# testeri_V1_1.net
KiCad netlist of a schematic drawn in EAGLE
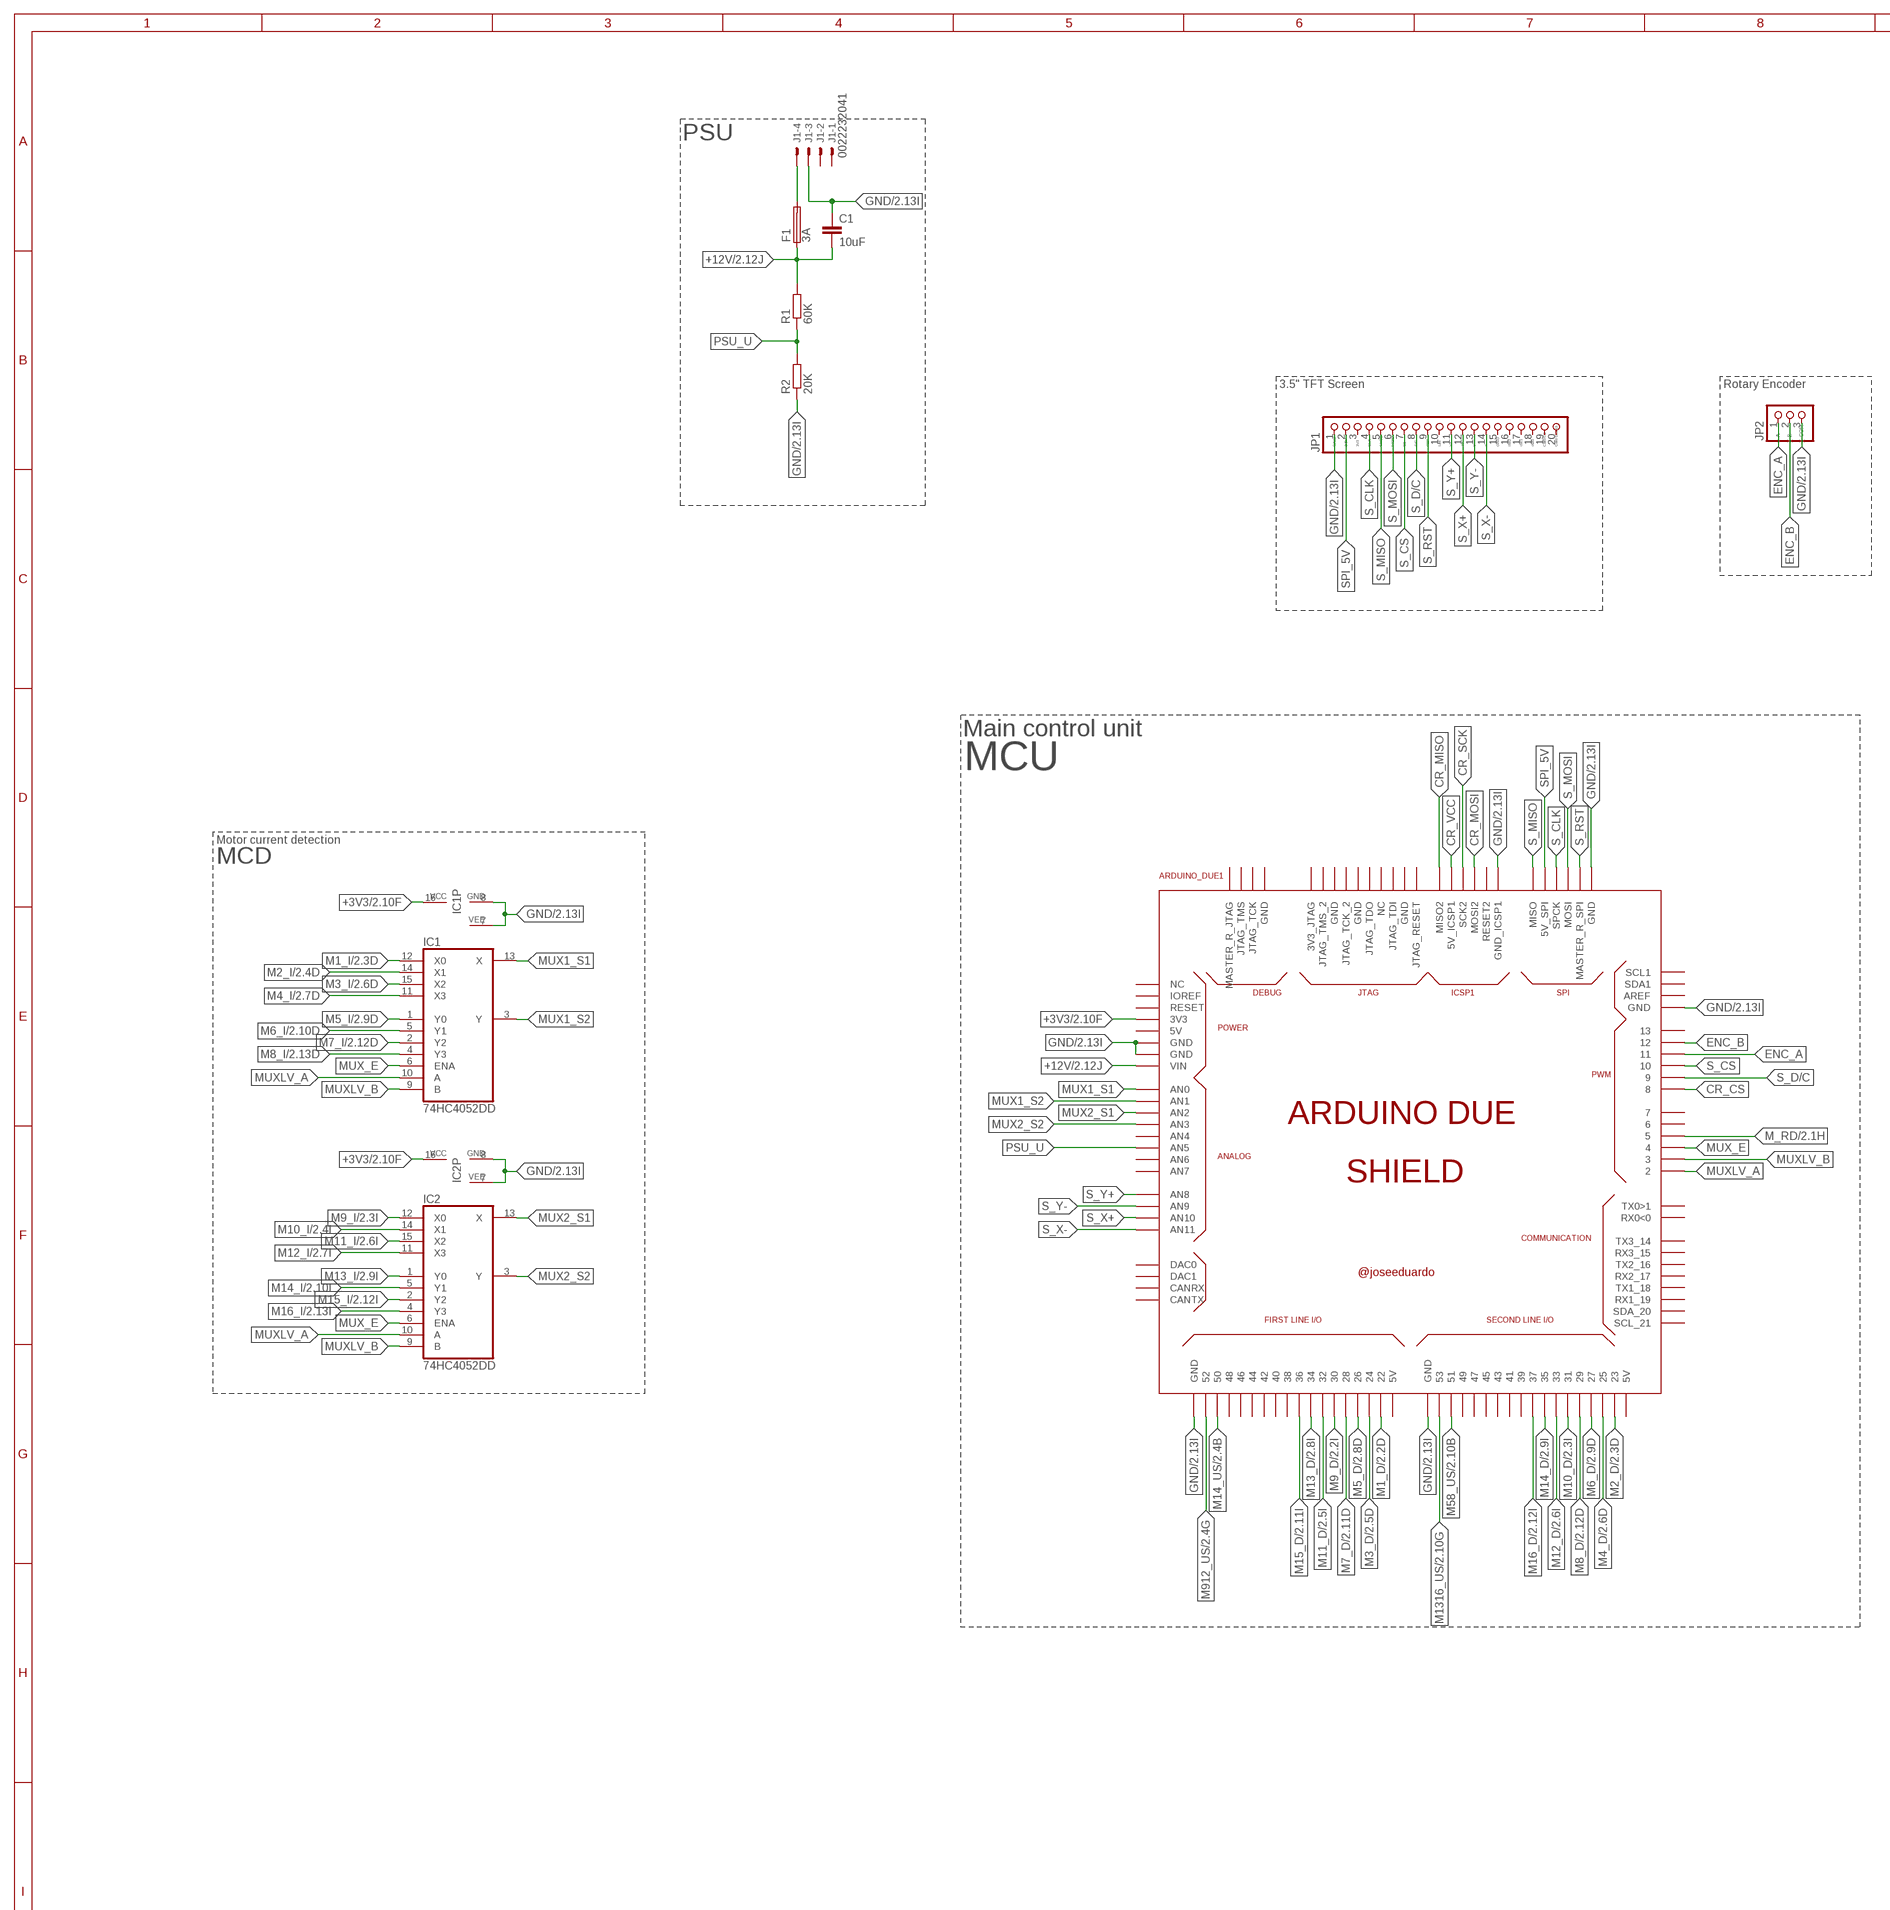
[diagram p0: schematic, sheet 1, part 1 of 2]
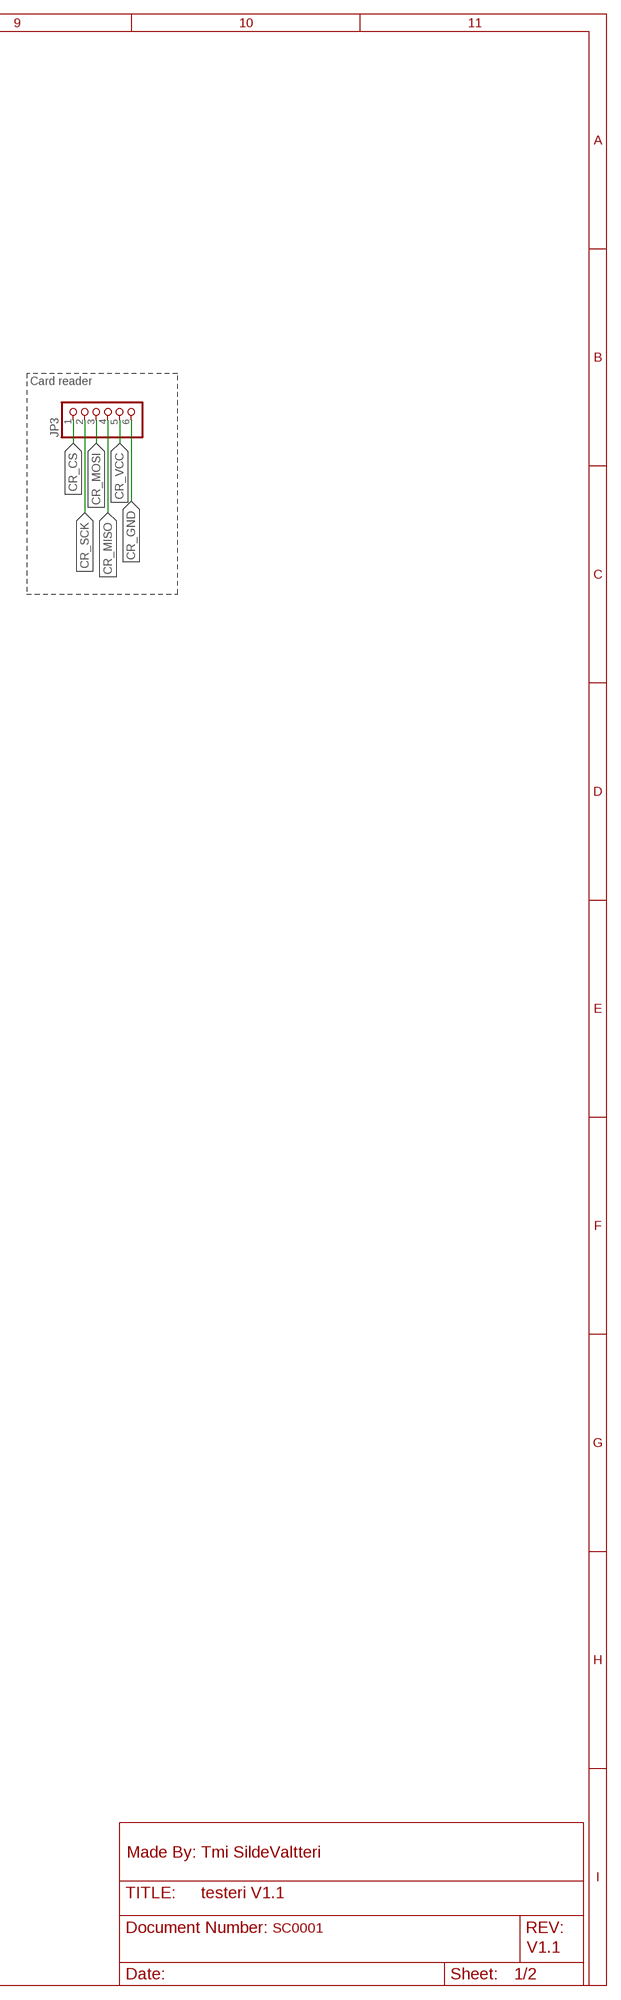
[diagram p1: schematic, sheet 1, part 2 of 2]
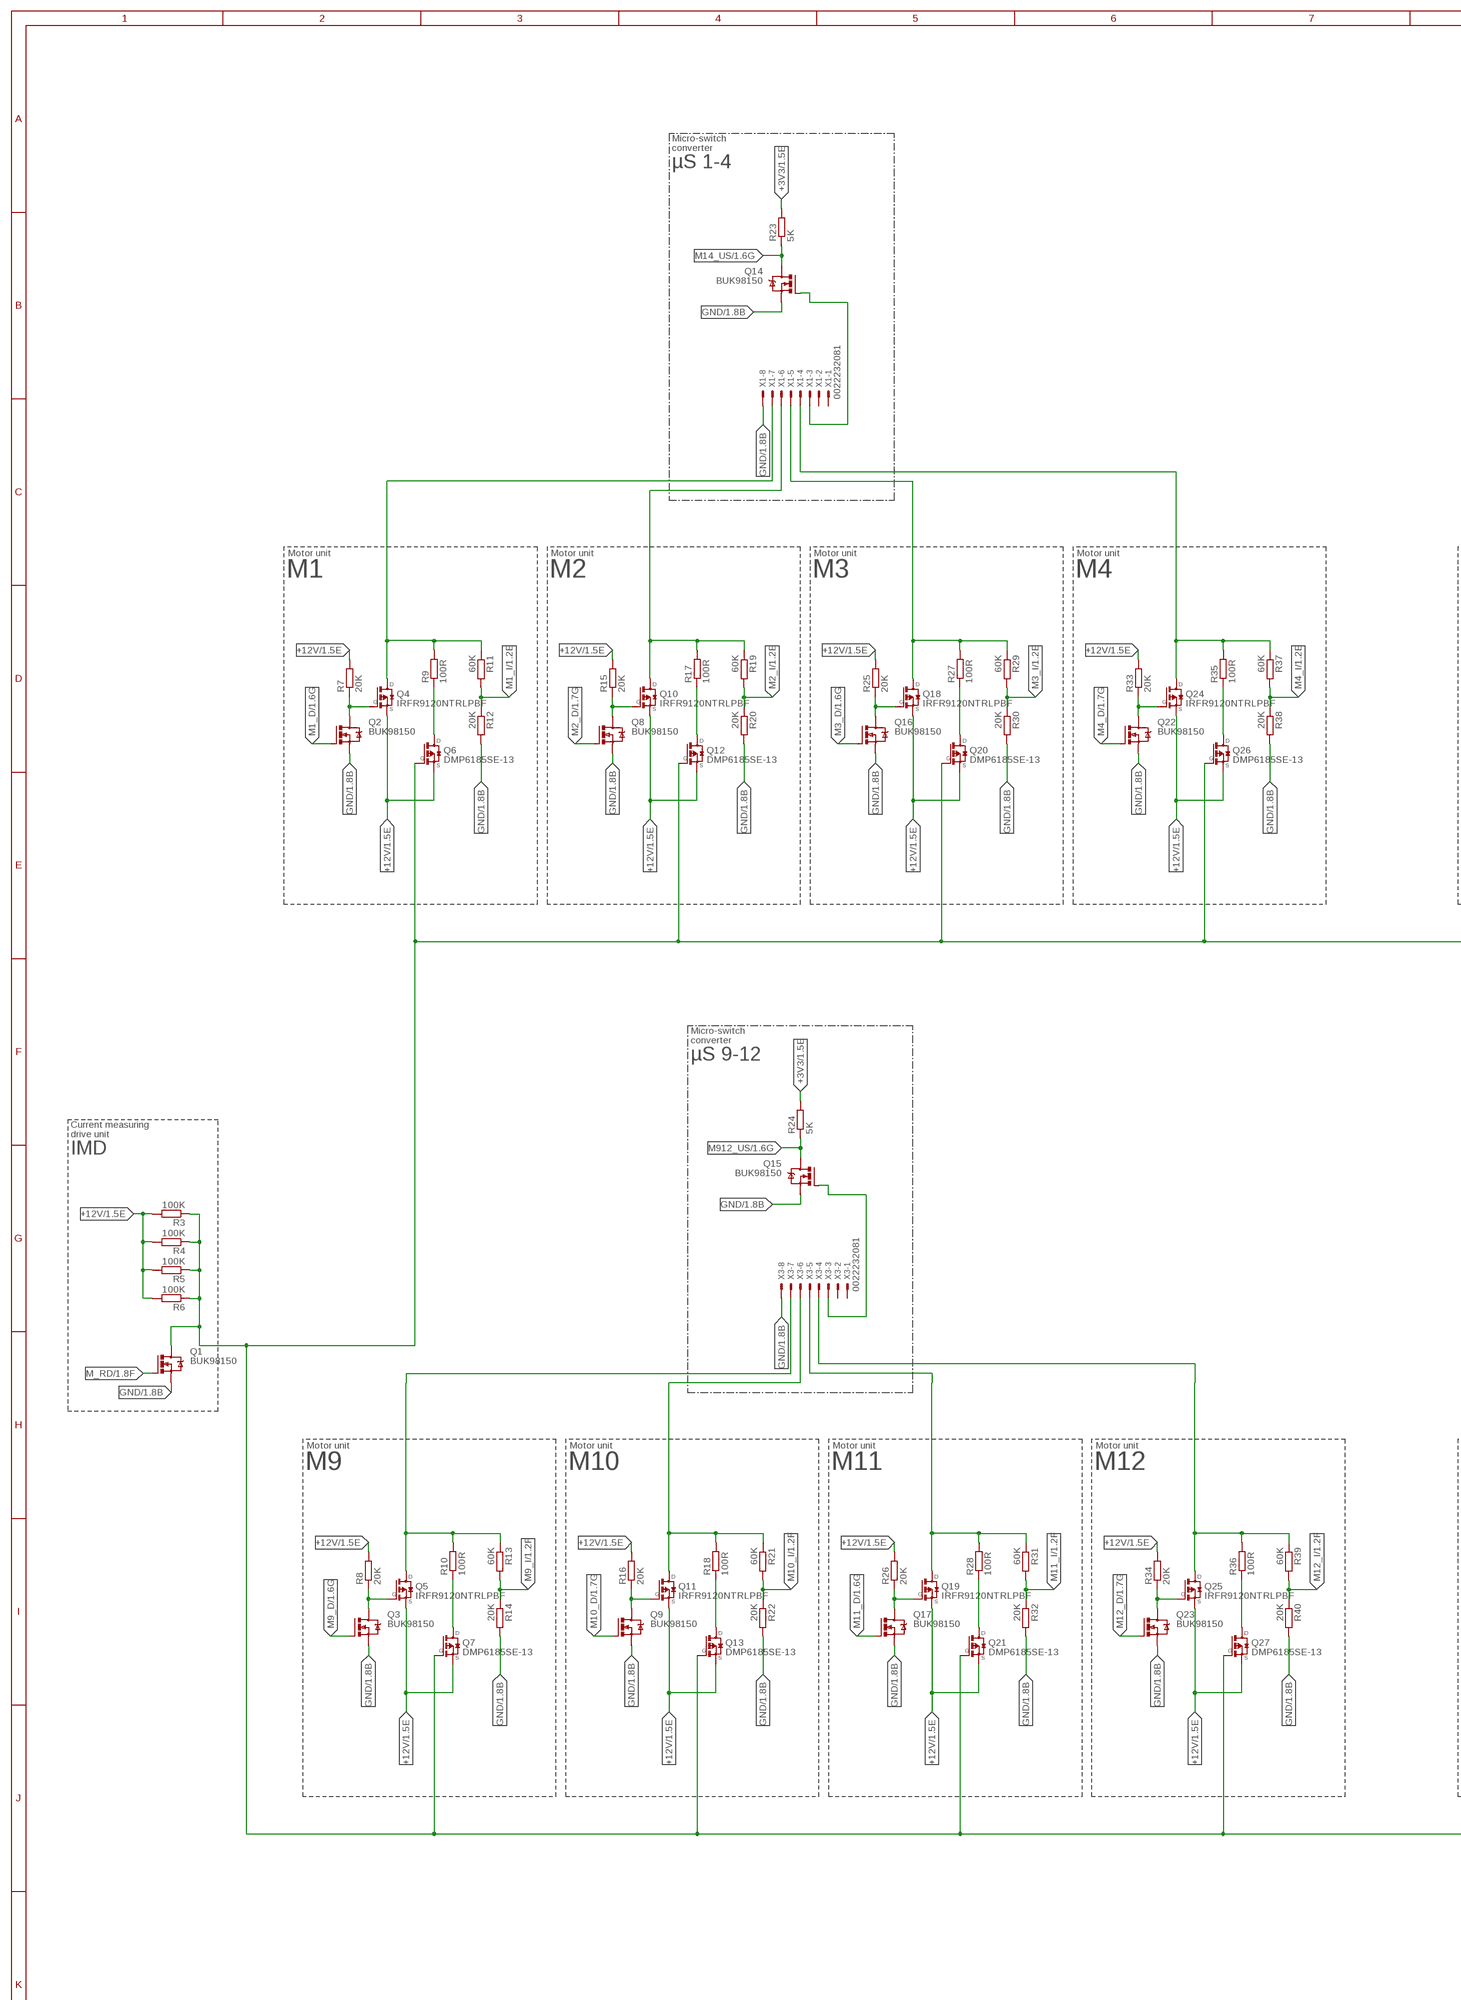
[diagram p2: schematic, sheet 2, part 1 of 3]
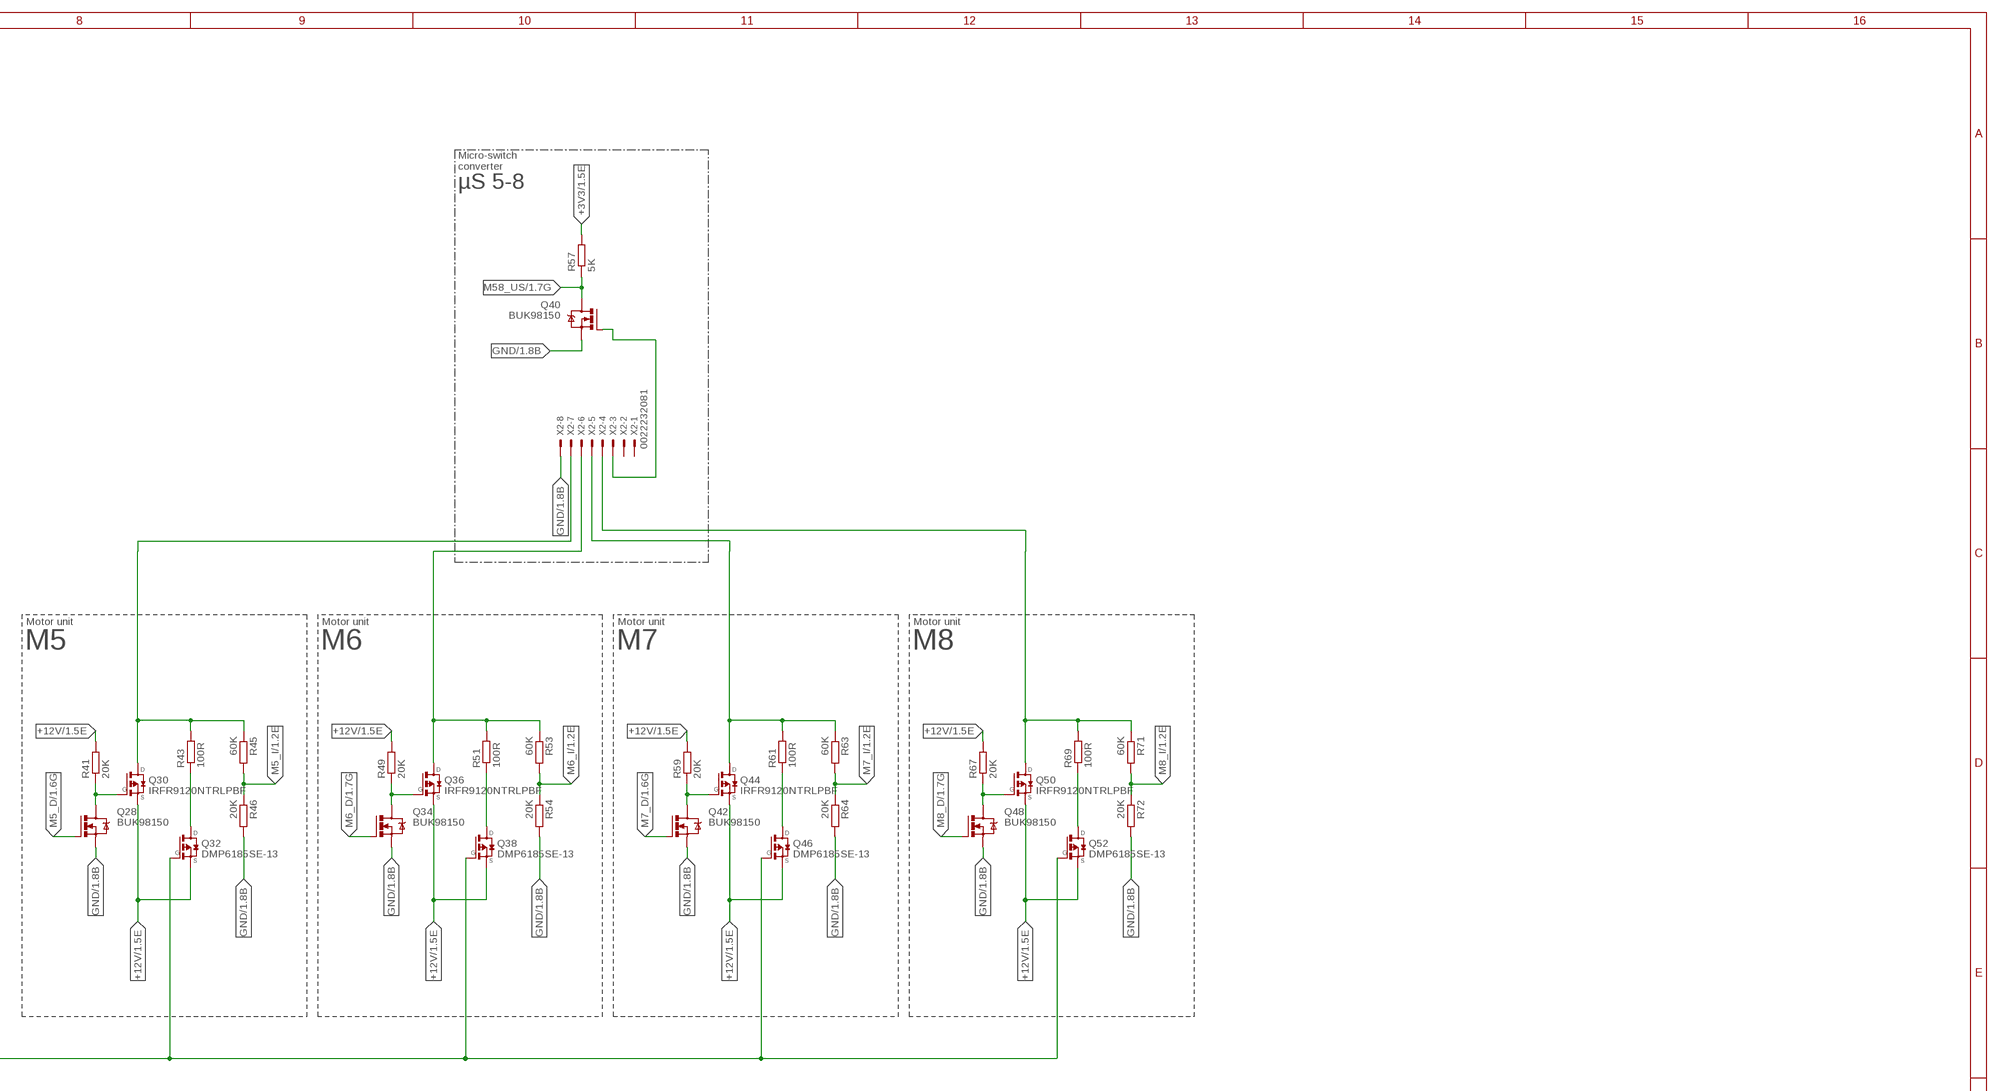
[diagram p3: schematic, sheet 2, part 2 of 3]
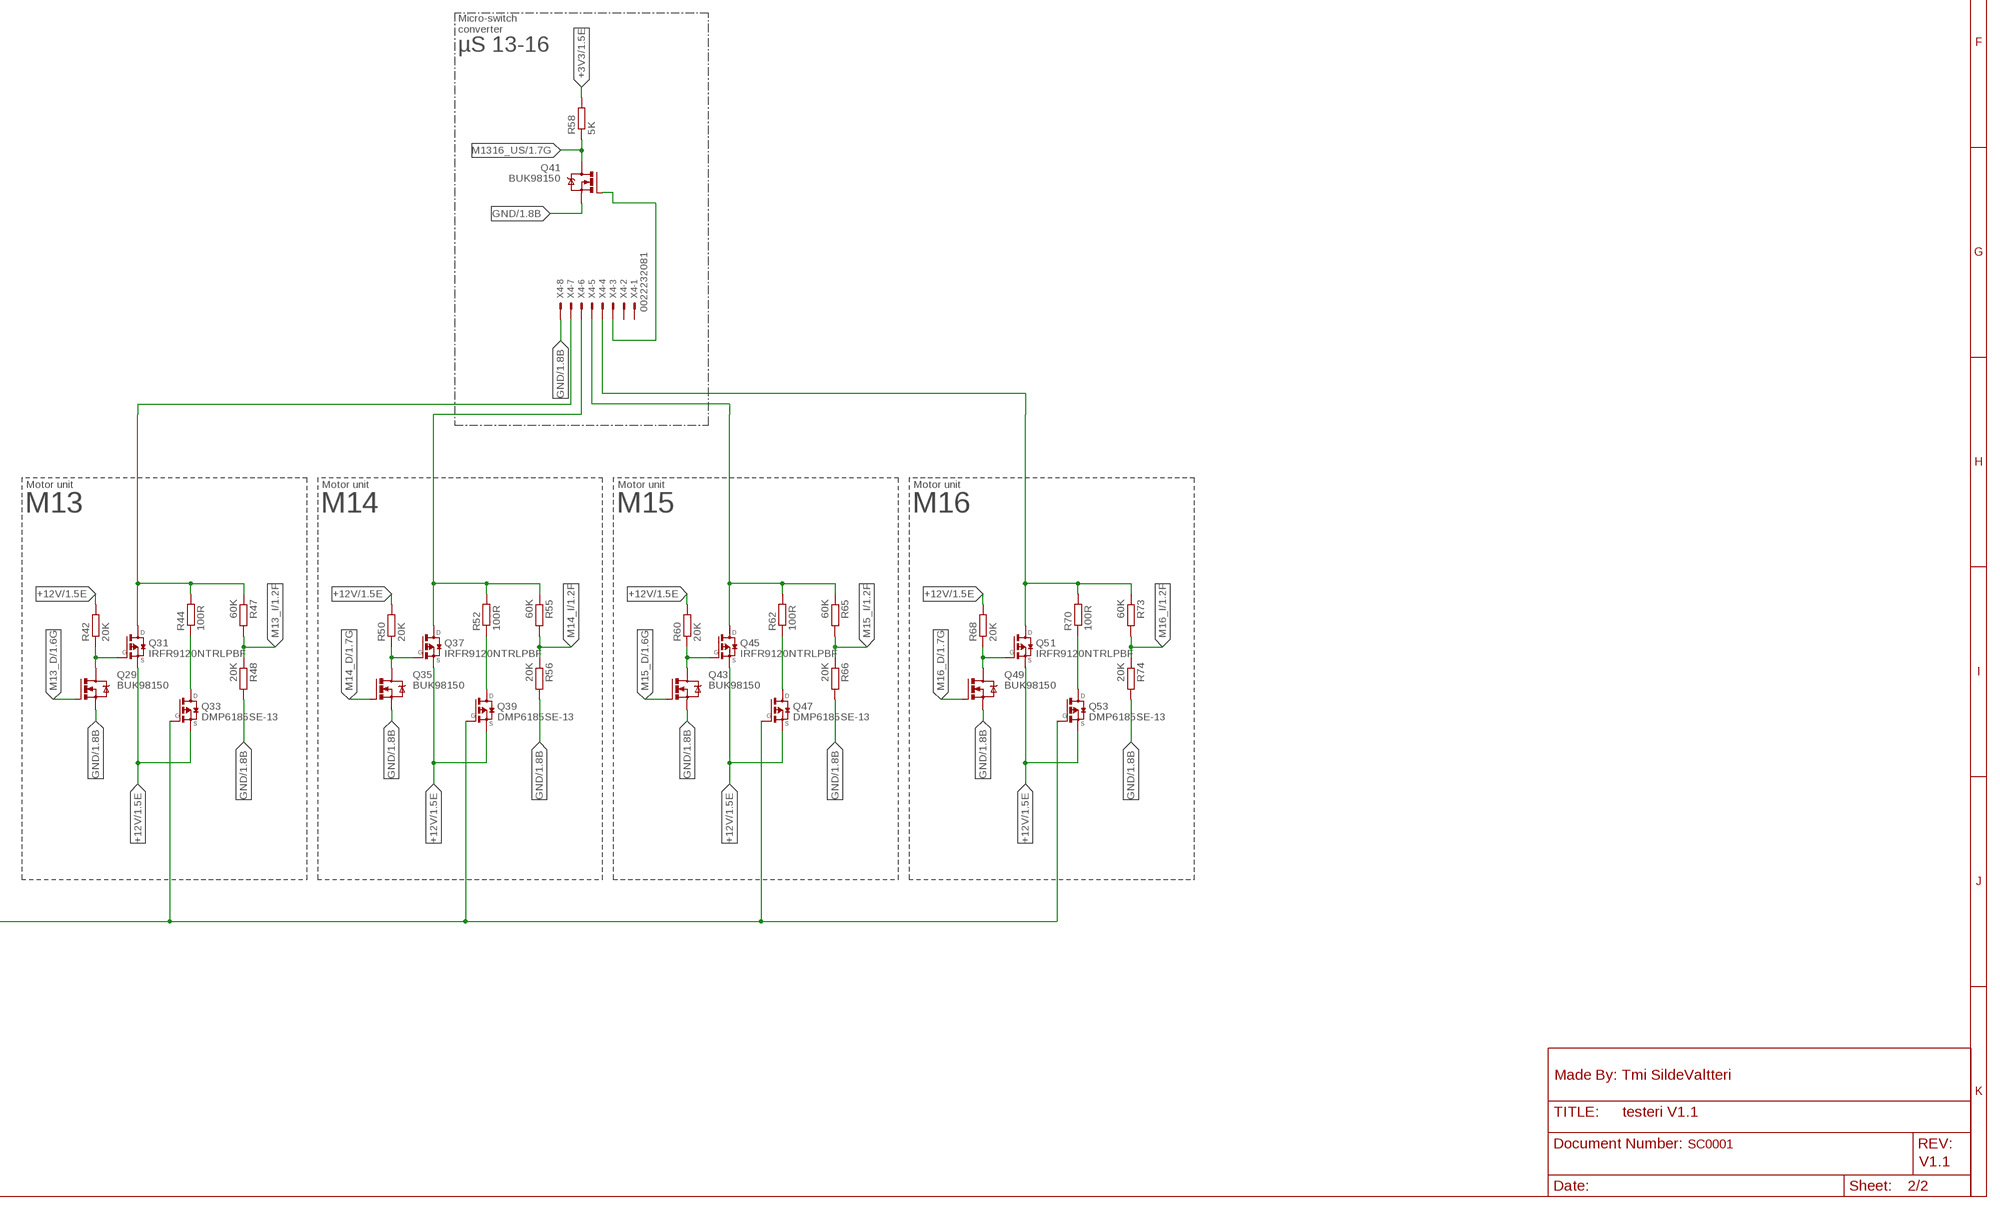
[diagram p4: schematic, sheet 2, part 3 of 3]

(export (version "E")
  (design (tool "Eeschema 10.0.6"))
  (components
    (comp (ref "Q1")
      (value "BUK98150")
      (footprint "eagle-import:SOT223")
      (libsource (lib "eagle-import") (part "BUK98150"))
    )
    (comp (ref "Q2")
      (value "BUK98150")
      (footprint "eagle-import:SOT223")
      (libsource (lib "eagle-import") (part "BUK98150"))
    )
    (comp (ref "Q3")
      (value "BUK98150")
      (footprint "eagle-import:SOT223")
      (libsource (lib "eagle-import") (part "BUK98150"))
    )
    (comp (ref "Q4")
      (value "IRFR9120NTRLPBF")
      (footprint "eagle-import:D-PAK_TO252AA")
      (libsource (lib "eagle-import") (part "IRFR9120NTRLPBF"))
    )
    (comp (ref "Q5")
      (value "IRFR9120NTRLPBF")
      (footprint "eagle-import:D-PAK_TO252AA")
      (libsource (lib "eagle-import") (part "IRFR9120NTRLPBF"))
    )
    (comp (ref "Q6")
      (value "DMP6185SE-13")
      (footprint "eagle-import:SOT223")
      (libsource (lib "eagle-import") (part "DMP6185SE-13"))
    )
    (comp (ref "Q7")
      (value "DMP6185SE-13")
      (footprint "eagle-import:SOT223")
      (libsource (lib "eagle-import") (part "DMP6185SE-13"))
    )
    (comp (ref "Q8")
      (value "BUK98150")
      (footprint "eagle-import:SOT223")
      (libsource (lib "eagle-import") (part "BUK98150"))
    )
    (comp (ref "Q9")
      (value "BUK98150")
      (footprint "eagle-import:SOT223")
      (libsource (lib "eagle-import") (part "BUK98150"))
    )
    (comp (ref "Q10")
      (value "IRFR9120NTRLPBF")
      (footprint "eagle-import:D-PAK_TO252AA")
      (libsource (lib "eagle-import") (part "IRFR9120NTRLPBF"))
    )
    (comp (ref "Q11")
      (value "IRFR9120NTRLPBF")
      (footprint "eagle-import:D-PAK_TO252AA")
      (libsource (lib "eagle-import") (part "IRFR9120NTRLPBF"))
    )
    (comp (ref "Q12")
      (value "DMP6185SE-13")
      (footprint "eagle-import:SOT223")
      (libsource (lib "eagle-import") (part "DMP6185SE-13"))
    )
    (comp (ref "Q13")
      (value "DMP6185SE-13")
      (footprint "eagle-import:SOT223")
      (libsource (lib "eagle-import") (part "DMP6185SE-13"))
    )
    (comp (ref "Q14")
      (value "BUK98150")
      (footprint "eagle-import:SOT223")
      (libsource (lib "eagle-import") (part "BUK98150"))
    )
    (comp (ref "Q15")
      (value "BUK98150")
      (footprint "eagle-import:SOT223")
      (libsource (lib "eagle-import") (part "BUK98150"))
    )
    (comp (ref "Q16")
      (value "BUK98150")
      (footprint "eagle-import:SOT223")
      (libsource (lib "eagle-import") (part "BUK98150"))
    )
    (comp (ref "Q17")
      (value "BUK98150")
      (footprint "eagle-import:SOT223")
      (libsource (lib "eagle-import") (part "BUK98150"))
    )
    (comp (ref "Q18")
      (value "IRFR9120NTRLPBF")
      (footprint "eagle-import:D-PAK_TO252AA")
      (libsource (lib "eagle-import") (part "IRFR9120NTRLPBF"))
    )
    (comp (ref "Q19")
      (value "IRFR9120NTRLPBF")
      (footprint "eagle-import:D-PAK_TO252AA")
      (libsource (lib "eagle-import") (part "IRFR9120NTRLPBF"))
    )
    (comp (ref "Q20")
      (value "DMP6185SE-13")
      (footprint "eagle-import:SOT223")
      (libsource (lib "eagle-import") (part "DMP6185SE-13"))
    )
    (comp (ref "Q21")
      (value "DMP6185SE-13")
      (footprint "eagle-import:SOT223")
      (libsource (lib "eagle-import") (part "DMP6185SE-13"))
    )
    (comp (ref "Q22")
      (value "BUK98150")
      (footprint "eagle-import:SOT223")
      (libsource (lib "eagle-import") (part "BUK98150"))
    )
    (comp (ref "Q23")
      (value "BUK98150")
      (footprint "eagle-import:SOT223")
      (libsource (lib "eagle-import") (part "BUK98150"))
    )
    (comp (ref "Q24")
      (value "IRFR9120NTRLPBF")
      (footprint "eagle-import:D-PAK_TO252AA")
      (libsource (lib "eagle-import") (part "IRFR9120NTRLPBF"))
    )
    (comp (ref "Q25")
      (value "IRFR9120NTRLPBF")
      (footprint "eagle-import:D-PAK_TO252AA")
      (libsource (lib "eagle-import") (part "IRFR9120NTRLPBF"))
    )
    (comp (ref "Q26")
      (value "DMP6185SE-13")
      (footprint "eagle-import:SOT223")
      (libsource (lib "eagle-import") (part "DMP6185SE-13"))
    )
    (comp (ref "Q27")
      (value "DMP6185SE-13")
      (footprint "eagle-import:SOT223")
      (libsource (lib "eagle-import") (part "DMP6185SE-13"))
    )
    (comp (ref "Q28")
      (value "BUK98150")
      (footprint "eagle-import:SOT223")
      (libsource (lib "eagle-import") (part "BUK98150"))
    )
    (comp (ref "Q29")
      (value "BUK98150")
      (footprint "eagle-import:SOT223")
      (libsource (lib "eagle-import") (part "BUK98150"))
    )
    (comp (ref "Q30")
      (value "IRFR9120NTRLPBF")
      (footprint "eagle-import:D-PAK_TO252AA")
      (libsource (lib "eagle-import") (part "IRFR9120NTRLPBF"))
    )
    (comp (ref "Q31")
      (value "IRFR9120NTRLPBF")
      (footprint "eagle-import:D-PAK_TO252AA")
      (libsource (lib "eagle-import") (part "IRFR9120NTRLPBF"))
    )
    (comp (ref "Q32")
      (value "DMP6185SE-13")
      (footprint "eagle-import:SOT223")
      (libsource (lib "eagle-import") (part "DMP6185SE-13"))
    )
    (comp (ref "Q33")
      (value "DMP6185SE-13")
      (footprint "eagle-import:SOT223")
      (libsource (lib "eagle-import") (part "DMP6185SE-13"))
    )
    (comp (ref "Q34")
      (value "BUK98150")
      (footprint "eagle-import:SOT223")
      (libsource (lib "eagle-import") (part "BUK98150"))
    )
    (comp (ref "Q35")
      (value "BUK98150")
      (footprint "eagle-import:SOT223")
      (libsource (lib "eagle-import") (part "BUK98150"))
    )
    (comp (ref "Q36")
      (value "IRFR9120NTRLPBF")
      (footprint "eagle-import:D-PAK_TO252AA")
      (libsource (lib "eagle-import") (part "IRFR9120NTRLPBF"))
    )
    (comp (ref "Q37")
      (value "IRFR9120NTRLPBF")
      (footprint "eagle-import:D-PAK_TO252AA")
      (libsource (lib "eagle-import") (part "IRFR9120NTRLPBF"))
    )
    (comp (ref "Q38")
      (value "DMP6185SE-13")
      (footprint "eagle-import:SOT223")
      (libsource (lib "eagle-import") (part "DMP6185SE-13"))
    )
    (comp (ref "Q39")
      (value "DMP6185SE-13")
      (footprint "eagle-import:SOT223")
      (libsource (lib "eagle-import") (part "DMP6185SE-13"))
    )
    (comp (ref "Q40")
      (value "BUK98150")
      (footprint "eagle-import:SOT223")
      (libsource (lib "eagle-import") (part "BUK98150"))
    )
    (comp (ref "Q41")
      (value "BUK98150")
      (footprint "eagle-import:SOT223")
      (libsource (lib "eagle-import") (part "BUK98150"))
    )
    (comp (ref "Q42")
      (value "BUK98150")
      (footprint "eagle-import:SOT223")
      (libsource (lib "eagle-import") (part "BUK98150"))
    )
    (comp (ref "Q43")
      (value "BUK98150")
      (footprint "eagle-import:SOT223")
      (libsource (lib "eagle-import") (part "BUK98150"))
    )
    (comp (ref "Q44")
      (value "IRFR9120NTRLPBF")
      (footprint "eagle-import:D-PAK_TO252AA")
      (libsource (lib "eagle-import") (part "IRFR9120NTRLPBF"))
    )
    (comp (ref "Q45")
      (value "IRFR9120NTRLPBF")
      (footprint "eagle-import:D-PAK_TO252AA")
      (libsource (lib "eagle-import") (part "IRFR9120NTRLPBF"))
    )
    (comp (ref "Q46")
      (value "DMP6185SE-13")
      (footprint "eagle-import:SOT223")
      (libsource (lib "eagle-import") (part "DMP6185SE-13"))
    )
    (comp (ref "Q47")
      (value "DMP6185SE-13")
      (footprint "eagle-import:SOT223")
      (libsource (lib "eagle-import") (part "DMP6185SE-13"))
    )
    (comp (ref "Q48")
      (value "BUK98150")
      (footprint "eagle-import:SOT223")
      (libsource (lib "eagle-import") (part "BUK98150"))
    )
    (comp (ref "Q49")
      (value "BUK98150")
      (footprint "eagle-import:SOT223")
      (libsource (lib "eagle-import") (part "BUK98150"))
    )
    (comp (ref "Q50")
      (value "IRFR9120NTRLPBF")
      (footprint "eagle-import:D-PAK_TO252AA")
      (libsource (lib "eagle-import") (part "IRFR9120NTRLPBF"))
    )
    (comp (ref "Q51")
      (value "IRFR9120NTRLPBF")
      (footprint "eagle-import:D-PAK_TO252AA")
      (libsource (lib "eagle-import") (part "IRFR9120NTRLPBF"))
    )
    (comp (ref "Q52")
      (value "DMP6185SE-13")
      (footprint "eagle-import:SOT223")
      (libsource (lib "eagle-import") (part "DMP6185SE-13"))
    )
    (comp (ref "Q53")
      (value "DMP6185SE-13")
      (footprint "eagle-import:SOT223")
      (libsource (lib "eagle-import") (part "DMP6185SE-13"))
    )
    (comp (ref "R3")
      (value "100K")
      (footprint "eagle-import:R3216W")
      (libsource (lib "eagle-import") (part "R-EU_R3216W"))
    )
    (comp (ref "R4")
      (value "100K")
      (footprint "eagle-import:R3216W")
      (libsource (lib "eagle-import") (part "R-EU_R3216W"))
    )
    (comp (ref "R5")
      (value "100K")
      (footprint "eagle-import:R3216W")
      (libsource (lib "eagle-import") (part "R-EU_R3216W"))
    )
    (comp (ref "R6")
      (value "100K")
      (footprint "eagle-import:R3216W")
      (libsource (lib "eagle-import") (part "R-EU_R3216W"))
    )
    (comp (ref "R7")
      (value "20K")
      (footprint "eagle-import:R3216W")
      (libsource (lib "eagle-import") (part "R-EU_R3216W"))
    )
    (comp (ref "R8")
      (value "20K")
      (footprint "eagle-import:R3216W")
      (libsource (lib "eagle-import") (part "R-EU_R3216W"))
    )
    (comp (ref "R9")
      (value "100R")
      (footprint "eagle-import:0411_15")
      (libsource (lib "eagle-import") (part "R-EU_0411/15"))
    )
    (comp (ref "R10")
      (value "100R")
      (footprint "eagle-import:0411_15")
      (libsource (lib "eagle-import") (part "R-EU_0411/15"))
    )
    (comp (ref "R11")
      (value "60K")
      (footprint "eagle-import:R3216W")
      (libsource (lib "eagle-import") (part "R-EU_R3216W"))
    )
    (comp (ref "R12")
      (value "20K")
      (footprint "eagle-import:R3216W")
      (libsource (lib "eagle-import") (part "R-EU_R3216W"))
    )
    (comp (ref "R13")
      (value "60K")
      (footprint "eagle-import:R3216W")
      (libsource (lib "eagle-import") (part "R-EU_R3216W"))
    )
    (comp (ref "R14")
      (value "20K")
      (footprint "eagle-import:R3216W")
      (libsource (lib "eagle-import") (part "R-EU_R3216W"))
    )
    (comp (ref "R15")
      (value "20K")
      (footprint "eagle-import:R3216W")
      (libsource (lib "eagle-import") (part "R-EU_R3216W"))
    )
    (comp (ref "R16")
      (value "20K")
      (footprint "eagle-import:R3216W")
      (libsource (lib "eagle-import") (part "R-EU_R3216W"))
    )
    (comp (ref "R17")
      (value "100R")
      (footprint "eagle-import:0411_15")
      (libsource (lib "eagle-import") (part "R-EU_0411/15"))
    )
    (comp (ref "R18")
      (value "100R")
      (footprint "eagle-import:0411_15")
      (libsource (lib "eagle-import") (part "R-EU_0411/15"))
    )
    (comp (ref "R19")
      (value "60K")
      (footprint "eagle-import:R3216W")
      (libsource (lib "eagle-import") (part "R-EU_R3216W"))
    )
    (comp (ref "R20")
      (value "20K")
      (footprint "eagle-import:R3216W")
      (libsource (lib "eagle-import") (part "R-EU_R3216W"))
    )
    (comp (ref "R21")
      (value "60K")
      (footprint "eagle-import:R3216W")
      (libsource (lib "eagle-import") (part "R-EU_R3216W"))
    )
    (comp (ref "R22")
      (value "20K")
      (footprint "eagle-import:R3216W")
      (libsource (lib "eagle-import") (part "R-EU_R3216W"))
    )
    (comp (ref "R23")
      (value "5K")
      (footprint "eagle-import:R3216W")
      (libsource (lib "eagle-import") (part "R-EU_R3216W"))
    )
    (comp (ref "R24")
      (value "5K")
      (footprint "eagle-import:R3216W")
      (libsource (lib "eagle-import") (part "R-EU_R3216W"))
    )
    (comp (ref "R25")
      (value "20K")
      (footprint "eagle-import:R3216W")
      (libsource (lib "eagle-import") (part "R-EU_R3216W"))
    )
    (comp (ref "R26")
      (value "20K")
      (footprint "eagle-import:R3216W")
      (libsource (lib "eagle-import") (part "R-EU_R3216W"))
    )
    (comp (ref "R27")
      (value "100R")
      (footprint "eagle-import:0411_15")
      (libsource (lib "eagle-import") (part "R-EU_0411/15"))
    )
    (comp (ref "R28")
      (value "100R")
      (footprint "eagle-import:0411_15")
      (libsource (lib "eagle-import") (part "R-EU_0411/15"))
    )
    (comp (ref "R29")
      (value "60K")
      (footprint "eagle-import:R3216W")
      (libsource (lib "eagle-import") (part "R-EU_R3216W"))
    )
    (comp (ref "R30")
      (value "20K")
      (footprint "eagle-import:R3216W")
      (libsource (lib "eagle-import") (part "R-EU_R3216W"))
    )
    (comp (ref "R31")
      (value "60K")
      (footprint "eagle-import:R3216W")
      (libsource (lib "eagle-import") (part "R-EU_R3216W"))
    )
    (comp (ref "R32")
      (value "20K")
      (footprint "eagle-import:R3216W")
      (libsource (lib "eagle-import") (part "R-EU_R3216W"))
    )
    (comp (ref "R33")
      (value "20K")
      (footprint "eagle-import:R3216W")
      (libsource (lib "eagle-import") (part "R-EU_R3216W"))
    )
    (comp (ref "R34")
      (value "20K")
      (footprint "eagle-import:R3216W")
      (libsource (lib "eagle-import") (part "R-EU_R3216W"))
    )
    (comp (ref "R35")
      (value "100R")
      (footprint "eagle-import:0411_15")
      (libsource (lib "eagle-import") (part "R-EU_0411/15"))
    )
    (comp (ref "R36")
      (value "100R")
      (footprint "eagle-import:0411_15")
      (libsource (lib "eagle-import") (part "R-EU_0411/15"))
    )
    (comp (ref "R37")
      (value "60K")
      (footprint "eagle-import:R3216W")
      (libsource (lib "eagle-import") (part "R-EU_R3216W"))
    )
    (comp (ref "R38")
      (value "20K")
      (footprint "eagle-import:R3216W")
      (libsource (lib "eagle-import") (part "R-EU_R3216W"))
    )
    (comp (ref "R39")
      (value "60K")
      (footprint "eagle-import:R3216W")
      (libsource (lib "eagle-import") (part "R-EU_R3216W"))
    )
    (comp (ref "R40")
      (value "20K")
      (footprint "eagle-import:R3216W")
      (libsource (lib "eagle-import") (part "R-EU_R3216W"))
    )
    (comp (ref "R41")
      (value "20K")
      (footprint "eagle-import:R3216W")
      (libsource (lib "eagle-import") (part "R-EU_R3216W"))
    )
    (comp (ref "R42")
      (value "20K")
      (footprint "eagle-import:R3216W")
      (libsource (lib "eagle-import") (part "R-EU_R3216W"))
    )
    (comp (ref "R43")
      (value "100R")
      (footprint "eagle-import:0411_15")
      (libsource (lib "eagle-import") (part "R-EU_0411/15"))
    )
    (comp (ref "R44")
      (value "100R")
      (footprint "eagle-import:0411_15")
      (libsource (lib "eagle-import") (part "R-EU_0411/15"))
    )
    (comp (ref "R45")
      (value "60K")
      (footprint "eagle-import:R3216W")
      (libsource (lib "eagle-import") (part "R-EU_R3216W"))
    )
    (comp (ref "R46")
      (value "20K")
      (footprint "eagle-import:R3216W")
      (libsource (lib "eagle-import") (part "R-EU_R3216W"))
    )
    (comp (ref "R47")
      (value "60K")
      (footprint "eagle-import:R3216W")
      (libsource (lib "eagle-import") (part "R-EU_R3216W"))
    )
    (comp (ref "R48")
      (value "20K")
      (footprint "eagle-import:R3216W")
      (libsource (lib "eagle-import") (part "R-EU_R3216W"))
    )
    (comp (ref "R49")
      (value "20K")
      (footprint "eagle-import:R3216W")
      (libsource (lib "eagle-import") (part "R-EU_R3216W"))
    )
    (comp (ref "R50")
      (value "20K")
      (footprint "eagle-import:R3216W")
      (libsource (lib "eagle-import") (part "R-EU_R3216W"))
    )
    (comp (ref "R51")
      (value "100R")
      (footprint "eagle-import:0411_15")
      (libsource (lib "eagle-import") (part "R-EU_0411/15"))
    )
    (comp (ref "R52")
      (value "100R")
      (footprint "eagle-import:0411_15")
      (libsource (lib "eagle-import") (part "R-EU_0411/15"))
    )
    (comp (ref "R53")
      (value "60K")
      (footprint "eagle-import:R3216W")
      (libsource (lib "eagle-import") (part "R-EU_R3216W"))
    )
    (comp (ref "R54")
      (value "20K")
      (footprint "eagle-import:R3216W")
      (libsource (lib "eagle-import") (part "R-EU_R3216W"))
    )
    (comp (ref "R55")
      (value "60K")
      (footprint "eagle-import:R3216W")
      (libsource (lib "eagle-import") (part "R-EU_R3216W"))
    )
    (comp (ref "R56")
      (value "20K")
      (footprint "eagle-import:R3216W")
      (libsource (lib "eagle-import") (part "R-EU_R3216W"))
    )
    (comp (ref "R57")
      (value "5K")
      (footprint "eagle-import:R3216W")
      (libsource (lib "eagle-import") (part "R-EU_R3216W"))
    )
    (comp (ref "R58")
      (value "5K")
      (footprint "eagle-import:R3216W")
      (libsource (lib "eagle-import") (part "R-EU_R3216W"))
    )
    (comp (ref "R59")
      (value "20K")
      (footprint "eagle-import:R3216W")
      (libsource (lib "eagle-import") (part "R-EU_R3216W"))
    )
    (comp (ref "R60")
      (value "20K")
      (footprint "eagle-import:R3216W")
      (libsource (lib "eagle-import") (part "R-EU_R3216W"))
    )
    (comp (ref "R61")
      (value "100R")
      (footprint "eagle-import:0411_15")
      (libsource (lib "eagle-import") (part "R-EU_0411/15"))
    )
    (comp (ref "R62")
      (value "100R")
      (footprint "eagle-import:0411_15")
      (libsource (lib "eagle-import") (part "R-EU_0411/15"))
    )
    (comp (ref "R63")
      (value "60K")
      (footprint "eagle-import:R3216W")
      (libsource (lib "eagle-import") (part "R-EU_R3216W"))
    )
    (comp (ref "R64")
      (value "20K")
      (footprint "eagle-import:R3216W")
      (libsource (lib "eagle-import") (part "R-EU_R3216W"))
    )
    (comp (ref "R65")
      (value "60K")
      (footprint "eagle-import:R3216W")
      (libsource (lib "eagle-import") (part "R-EU_R3216W"))
    )
    (comp (ref "R66")
      (value "20K")
      (footprint "eagle-import:R3216W")
      (libsource (lib "eagle-import") (part "R-EU_R3216W"))
    )
    (comp (ref "R67")
      (value "20K")
      (footprint "eagle-import:R3216W")
      (libsource (lib "eagle-import") (part "R-EU_R3216W"))
    )
    (comp (ref "R68")
      (value "20K")
      (footprint "eagle-import:R3216W")
      (libsource (lib "eagle-import") (part "R-EU_R3216W"))
    )
    (comp (ref "R69")
      (value "100R")
      (footprint "eagle-import:0411_15")
      (libsource (lib "eagle-import") (part "R-EU_0411/15"))
    )
    (comp (ref "R70")
      (value "100R")
      (footprint "eagle-import:0411_15")
      (libsource (lib "eagle-import") (part "R-EU_0411/15"))
    )
    (comp (ref "R71")
      (value "60K")
      (footprint "eagle-import:R3216W")
      (libsource (lib "eagle-import") (part "R-EU_R3216W"))
    )
    (comp (ref "R72")
      (value "20K")
      (footprint "eagle-import:R3216W")
      (libsource (lib "eagle-import") (part "R-EU_R3216W"))
    )
    (comp (ref "R73")
      (value "60K")
      (footprint "eagle-import:R3216W")
      (libsource (lib "eagle-import") (part "R-EU_R3216W"))
    )
    (comp (ref "R74")
      (value "20K")
      (footprint "eagle-import:R3216W")
      (libsource (lib "eagle-import") (part "R-EU_R3216W"))
    )
    (comp (ref "X1")
      (value "0022232081")
      (footprint "eagle-import:22-23-2081")
      (fields (field (name "MF") "MOLEX") (field (name "MPN") "22-23-2081"))
      (libsource (lib "eagle-import") (part "22-23-2081"))
    )
    (comp (ref "X2")
      (value "0022232081")
      (footprint "eagle-import:22-23-2081")
      (fields (field (name "MF") "MOLEX") (field (name "MPN") "22-23-2081"))
      (libsource (lib "eagle-import") (part "22-23-2081"))
    )
    (comp (ref "X3")
      (value "0022232081")
      (footprint "eagle-import:22-23-2081")
      (fields (field (name "MF") "MOLEX") (field (name "MPN") "22-23-2081"))
      (libsource (lib "eagle-import") (part "22-23-2081"))
    )
    (comp (ref "X4")
      (value "0022232081")
      (footprint "eagle-import:22-23-2081")
      (fields (field (name "MF") "MOLEX") (field (name "MPN") "22-23-2081"))
      (libsource (lib "eagle-import") (part "22-23-2081"))
    )
    (comp (ref "ARDUINO_DUE1")
      (value "ARDUINO_DUE_SHIELD")
      (footprint "eagle-import:ARDUINO_DUE_SHIELD")
      (libsource (lib "eagle-import") (part "ARDUINO_DUE_SHIELD"))
    )
    (comp (ref "C1")
      (value "10uF")
      (footprint "eagle-import:C3216")
      (libsource (lib "eagle-import") (part "C-EUC3216"))
    )
    (comp (ref "F1")
      (value "3A")
      (footprint "eagle-import:SH22,5")
      (fields (field (name "MF") "SCHURTER") (field (name "MPN") "0031.8201"))
      (libsource (lib "eagle-import") (part "SH22,5"))
    )
    (comp (ref "IC1")
      (value "74HC4052DD")
      (footprint "eagle-import:SO16")
      (libsource (lib "eagle-import") (part "74HC4052DD"))
    )
    (comp (ref "IC2")
      (value "74HC4052DD")
      (footprint "eagle-import:SO16")
      (libsource (lib "eagle-import") (part "74HC4052DD"))
    )
    (comp (ref "J1")
      (value "0022232041")
      (footprint "eagle-import:6410-04")
      (fields (field (name "MF") "MOLEX"))
      (libsource (lib "eagle-import") (part "22-?-0427-2041"))
    )
    (comp (ref "JP1")
      (value "PINHD-1X20")
      (footprint "eagle-import:1X20")
      (libsource (lib "eagle-import") (part "PINHD-1X20"))
    )
    (comp (ref "JP2")
      (value "PINHD-1X3")
      (footprint "eagle-import:1X03")
      (libsource (lib "eagle-import") (part "PINHD-1X3"))
    )
    (comp (ref "JP3")
      (value "PINHD-1X6")
      (footprint "eagle-import:1X06")
      (libsource (lib "eagle-import") (part "PINHD-1X6"))
    )
    (comp (ref "R1")
      (value "60K")
      (footprint "eagle-import:R3216W")
      (libsource (lib "eagle-import") (part "R-EU_R3216W"))
    )
    (comp (ref "R2")
      (value "20K")
      (footprint "eagle-import:R3216W")
      (libsource (lib "eagle-import") (part "R-EU_R3216W"))
    )
  )
  (nets
    (net (code "1") (name "+3V3") (class "Default")
      (node (ref "ARDUINO_DUE1") (pin "3V3") (pinfunction "3V3_3V3") (pintype "bidirectional"))
      (node (ref "IC1") (pin "16") (pinfunction "VCC_16") (pintype "power_in"))
      (node (ref "IC2") (pin "16") (pinfunction "VCC_16") (pintype "power_in"))
      (node (ref "R23") (pin "2") (pinfunction "2_2") (pintype "passive"))
      (node (ref "R24") (pin "2") (pinfunction "2_2") (pintype "passive"))
      (node (ref "R57") (pin "2") (pinfunction "2_2") (pintype "passive"))
      (node (ref "R58") (pin "2") (pinfunction "2_2") (pintype "passive"))
    )
    (net (code "2") (name "+12V") (class "Default")
      (node (ref "ARDUINO_DUE1") (pin "VIN") (pinfunction "VIN_VIN") (pintype "bidirectional"))
      (node (ref "C1") (pin "2") (pinfunction "2_2") (pintype "passive"))
      (node (ref "F1") (pin "1") (pinfunction "1_1") (pintype "passive"))
      (node (ref "Q10") (pin "3") (pinfunction "S_3") (pintype "passive"))
      (node (ref "Q11") (pin "3") (pinfunction "S_3") (pintype "passive"))
      (node (ref "Q12") (pin "3") (pinfunction "S_3") (pintype "passive"))
      (node (ref "Q13") (pin "3") (pinfunction "S_3") (pintype "passive"))
      (node (ref "Q18") (pin "3") (pinfunction "S_3") (pintype "passive"))
      (node (ref "Q19") (pin "3") (pinfunction "S_3") (pintype "passive"))
      (node (ref "Q20") (pin "3") (pinfunction "S_3") (pintype "passive"))
      (node (ref "Q21") (pin "3") (pinfunction "S_3") (pintype "passive"))
      (node (ref "Q24") (pin "3") (pinfunction "S_3") (pintype "passive"))
      (node (ref "Q25") (pin "3") (pinfunction "S_3") (pintype "passive"))
      (node (ref "Q26") (pin "3") (pinfunction "S_3") (pintype "passive"))
      (node (ref "Q27") (pin "3") (pinfunction "S_3") (pintype "passive"))
      (node (ref "Q30") (pin "3") (pinfunction "S_3") (pintype "passive"))
      (node (ref "Q31") (pin "3") (pinfunction "S_3") (pintype "passive"))
      (node (ref "Q32") (pin "3") (pinfunction "S_3") (pintype "passive"))
      (node (ref "Q33") (pin "3") (pinfunction "S_3") (pintype "passive"))
      (node (ref "Q36") (pin "3") (pinfunction "S_3") (pintype "passive"))
      (node (ref "Q37") (pin "3") (pinfunction "S_3") (pintype "passive"))
      (node (ref "Q38") (pin "3") (pinfunction "S_3") (pintype "passive"))
      (node (ref "Q39") (pin "3") (pinfunction "S_3") (pintype "passive"))
      (node (ref "Q4") (pin "3") (pinfunction "S_3") (pintype "passive"))
      (node (ref "Q44") (pin "3") (pinfunction "S_3") (pintype "passive"))
      (node (ref "Q45") (pin "3") (pinfunction "S_3") (pintype "passive"))
      (node (ref "Q46") (pin "3") (pinfunction "S_3") (pintype "passive"))
      (node (ref "Q47") (pin "3") (pinfunction "S_3") (pintype "passive"))
      (node (ref "Q5") (pin "3") (pinfunction "S_3") (pintype "passive"))
      (node (ref "Q50") (pin "3") (pinfunction "S_3") (pintype "passive"))
      (node (ref "Q51") (pin "3") (pinfunction "S_3") (pintype "passive"))
      (node (ref "Q52") (pin "3") (pinfunction "S_3") (pintype "passive"))
      (node (ref "Q53") (pin "3") (pinfunction "S_3") (pintype "passive"))
      (node (ref "Q6") (pin "3") (pinfunction "S_3") (pintype "passive"))
      (node (ref "Q7") (pin "3") (pinfunction "S_3") (pintype "passive"))
      (node (ref "R1") (pin "2") (pinfunction "2_2") (pintype "passive"))
      (node (ref "R15") (pin "2") (pinfunction "2_2") (pintype "passive"))
      (node (ref "R16") (pin "2") (pinfunction "2_2") (pintype "passive"))
      (node (ref "R25") (pin "2") (pinfunction "2_2") (pintype "passive"))
      (node (ref "R26") (pin "2") (pinfunction "2_2") (pintype "passive"))
      (node (ref "R3") (pin "2") (pinfunction "2_2") (pintype "passive"))
      (node (ref "R33") (pin "2") (pinfunction "2_2") (pintype "passive"))
      (node (ref "R34") (pin "2") (pinfunction "2_2") (pintype "passive"))
      (node (ref "R4") (pin "2") (pinfunction "2_2") (pintype "passive"))
      (node (ref "R41") (pin "2") (pinfunction "2_2") (pintype "passive"))
      (node (ref "R42") (pin "2") (pinfunction "2_2") (pintype "passive"))
      (node (ref "R49") (pin "2") (pinfunction "2_2") (pintype "passive"))
      (node (ref "R5") (pin "2") (pinfunction "2_2") (pintype "passive"))
      (node (ref "R50") (pin "2") (pinfunction "2_2") (pintype "passive"))
      (node (ref "R59") (pin "2") (pinfunction "2_2") (pintype "passive"))
      (node (ref "R6") (pin "2") (pinfunction "2_2") (pintype "passive"))
      (node (ref "R60") (pin "2") (pinfunction "2_2") (pintype "passive"))
      (node (ref "R67") (pin "2") (pinfunction "2_2") (pintype "passive"))
      (node (ref "R68") (pin "2") (pinfunction "2_2") (pintype "passive"))
      (node (ref "R7") (pin "2") (pinfunction "2_2") (pintype "passive"))
      (node (ref "R8") (pin "2") (pinfunction "2_2") (pintype "passive"))
    )
    (net (code "3") (name "CR_CS") (class "Default")
      (node (ref "ARDUINO_DUE1") (pin "8") (pinfunction "8_8") (pintype "bidirectional"))
      (node (ref "JP3") (pin "1") (pinfunction "1_1") (pintype "passive"))
    )
    (net (code "4") (name "CR_GND") (class "Default")
      (node (ref "JP3") (pin "6") (pinfunction "6_6") (pintype "passive"))
    )
    (net (code "5") (name "CR_MISO") (class "Default")
      (node (ref "ARDUINO_DUE1") (pin "MISO2") (pinfunction "MISO2_MISO2") (pintype "bidirectional"))
      (node (ref "JP3") (pin "4") (pinfunction "4_4") (pintype "passive"))
    )
    (net (code "6") (name "CR_MOSI") (class "Default")
      (node (ref "ARDUINO_DUE1") (pin "MOSI2") (pinfunction "MOSI2_MOSI2") (pintype "bidirectional"))
      (node (ref "JP3") (pin "3") (pinfunction "3_3") (pintype "passive"))
    )
    (net (code "7") (name "CR_SCK") (class "Default")
      (node (ref "ARDUINO_DUE1") (pin "SCK2") (pinfunction "SCK2_SCK2") (pintype "bidirectional"))
      (node (ref "JP3") (pin "2") (pinfunction "2_2") (pintype "passive"))
    )
    (net (code "8") (name "CR_VCC") (class "Default")
      (node (ref "ARDUINO_DUE1") (pin "5V_ICSP1") (pinfunction "5V_ICSP1_5V_ICSP1") (pintype "bidirectional"))
      (node (ref "JP3") (pin "5") (pinfunction "5_5") (pintype "passive"))
    )
    (net (code "9") (name "ENC_A") (class "Default")
      (node (ref "ARDUINO_DUE1") (pin "11") (pinfunction "11_11") (pintype "bidirectional"))
      (node (ref "JP2") (pin "1") (pinfunction "1_1") (pintype "passive"))
    )
    (net (code "10") (name "ENC_B") (class "Default")
      (node (ref "ARDUINO_DUE1") (pin "12") (pinfunction "12_12") (pintype "bidirectional"))
      (node (ref "JP2") (pin "2") (pinfunction "2_2") (pintype "passive"))
    )
    (net (code "11") (name "GND") (class "Default")
      (node (ref "ARDUINO_DUE1") (pin "GND") (pinfunction "GND_GND") (pintype "bidirectional"))
      (node (ref "ARDUINO_DUE1") (pin "GND_1") (pinfunction "GND_GND_1") (pintype "bidirectional"))
      (node (ref "ARDUINO_DUE1") (pin "GND_2") (pinfunction "GND_GND_2") (pintype "bidirectional"))
      (node (ref "ARDUINO_DUE1") (pin "GND_3") (pinfunction "GND_GND_3") (pintype "bidirectional"))
      (node (ref "ARDUINO_DUE1") (pin "GND_4") (pinfunction "GND_GND_4") (pintype "bidirectional"))
      (node (ref "ARDUINO_DUE1") (pin "GND_5") (pinfunction "GND_GND_5") (pintype "bidirectional"))
      (node (ref "ARDUINO_DUE1") (pin "GND_ICSP1") (pinfunction "GND_ICSP1_GND_ICSP1") (pintype "bidirectional"))
      (node (ref "C1") (pin "1") (pinfunction "1_1") (pintype "passive"))
      (node (ref "IC1") (pin "7") (pinfunction "VEE_7") (pintype "power_in"))
      (node (ref "IC1") (pin "8") (pinfunction "GND_8") (pintype "power_in"))
      (node (ref "IC2") (pin "7") (pinfunction "VEE_7") (pintype "power_in"))
      (node (ref "IC2") (pin "8") (pinfunction "GND_8") (pintype "power_in"))
      (node (ref "J1") (pin "3") (pinfunction "S_3") (pintype "passive"))
      (node (ref "JP1") (pin "1") (pinfunction "1_1") (pintype "passive"))
      (node (ref "JP2") (pin "3") (pinfunction "3_3") (pintype "passive"))
      (node (ref "Q1") (pin "3") (pinfunction "S_3") (pintype "passive"))
      (node (ref "Q14") (pin "3") (pinfunction "S_3") (pintype "passive"))
      (node (ref "Q15") (pin "3") (pinfunction "S_3") (pintype "passive"))
      (node (ref "Q16") (pin "3") (pinfunction "S_3") (pintype "passive"))
      (node (ref "Q17") (pin "3") (pinfunction "S_3") (pintype "passive"))
      (node (ref "Q2") (pin "3") (pinfunction "S_3") (pintype "passive"))
      (node (ref "Q22") (pin "3") (pinfunction "S_3") (pintype "passive"))
      (node (ref "Q23") (pin "3") (pinfunction "S_3") (pintype "passive"))
      (node (ref "Q28") (pin "3") (pinfunction "S_3") (pintype "passive"))
      (node (ref "Q29") (pin "3") (pinfunction "S_3") (pintype "passive"))
      (node (ref "Q3") (pin "3") (pinfunction "S_3") (pintype "passive"))
      (node (ref "Q34") (pin "3") (pinfunction "S_3") (pintype "passive"))
      (node (ref "Q35") (pin "3") (pinfunction "S_3") (pintype "passive"))
      (node (ref "Q40") (pin "3") (pinfunction "S_3") (pintype "passive"))
      (node (ref "Q41") (pin "3") (pinfunction "S_3") (pintype "passive"))
      (node (ref "Q42") (pin "3") (pinfunction "S_3") (pintype "passive"))
      (node (ref "Q43") (pin "3") (pinfunction "S_3") (pintype "passive"))
      (node (ref "Q48") (pin "3") (pinfunction "S_3") (pintype "passive"))
      (node (ref "Q49") (pin "3") (pinfunction "S_3") (pintype "passive"))
      (node (ref "Q8") (pin "3") (pinfunction "S_3") (pintype "passive"))
      (node (ref "Q9") (pin "3") (pinfunction "S_3") (pintype "passive"))
      (node (ref "R12") (pin "2") (pinfunction "2_2") (pintype "passive"))
      (node (ref "R14") (pin "2") (pinfunction "2_2") (pintype "passive"))
      (node (ref "R2") (pin "1") (pinfunction "1_1") (pintype "passive"))
      (node (ref "R20") (pin "2") (pinfunction "2_2") (pintype "passive"))
      (node (ref "R22") (pin "2") (pinfunction "2_2") (pintype "passive"))
      (node (ref "R30") (pin "2") (pinfunction "2_2") (pintype "passive"))
      (node (ref "R32") (pin "2") (pinfunction "2_2") (pintype "passive"))
      (node (ref "R38") (pin "2") (pinfunction "2_2") (pintype "passive"))
      (node (ref "R40") (pin "2") (pinfunction "2_2") (pintype "passive"))
      (node (ref "R46") (pin "2") (pinfunction "2_2") (pintype "passive"))
      (node (ref "R48") (pin "2") (pinfunction "2_2") (pintype "passive"))
      (node (ref "R54") (pin "2") (pinfunction "2_2") (pintype "passive"))
      (node (ref "R56") (pin "2") (pinfunction "2_2") (pintype "passive"))
      (node (ref "R64") (pin "2") (pinfunction "2_2") (pintype "passive"))
      (node (ref "R66") (pin "2") (pinfunction "2_2") (pintype "passive"))
      (node (ref "R72") (pin "2") (pinfunction "2_2") (pintype "passive"))
      (node (ref "R74") (pin "2") (pinfunction "2_2") (pintype "passive"))
      (node (ref "X1") (pin "8") (pinfunction "S_8") (pintype "passive"))
      (node (ref "X2") (pin "8") (pinfunction "S_8") (pintype "passive"))
      (node (ref "X3") (pin "8") (pinfunction "S_8") (pintype "passive"))
      (node (ref "X4") (pin "8") (pinfunction "S_8") (pintype "passive"))
    )
    (net (code "12") (name "M1_D") (class "Default")
      (node (ref "ARDUINO_DUE1") (pin "22") (pinfunction "22_22") (pintype "bidirectional"))
      (node (ref "Q2") (pin "1") (pinfunction "G_1") (pintype "passive"))
    )
    (net (code "13") (name "M1_I") (class "Default")
      (node (ref "IC1") (pin "12") (pinfunction "X0_12") (pintype "bidirectional"))
      (node (ref "R11") (pin "2") (pinfunction "2_2") (pintype "passive"))
      (node (ref "R12") (pin "1") (pinfunction "1_1") (pintype "passive"))
    )
    (net (code "14") (name "M2_D") (class "Default")
      (node (ref "ARDUINO_DUE1") (pin "23") (pinfunction "23_23") (pintype "bidirectional"))
      (node (ref "Q8") (pin "1") (pinfunction "G_1") (pintype "passive"))
    )
    (net (code "15") (name "M2_I") (class "Default")
      (node (ref "IC1") (pin "14") (pinfunction "X1_14") (pintype "bidirectional"))
      (node (ref "R19") (pin "2") (pinfunction "2_2") (pintype "passive"))
      (node (ref "R20") (pin "1") (pinfunction "1_1") (pintype "passive"))
    )
    (net (code "16") (name "M3_D") (class "Default")
      (node (ref "ARDUINO_DUE1") (pin "24") (pinfunction "24_24") (pintype "bidirectional"))
      (node (ref "Q16") (pin "1") (pinfunction "G_1") (pintype "passive"))
    )
    (net (code "17") (name "M3_I") (class "Default")
      (node (ref "IC1") (pin "15") (pinfunction "X2_15") (pintype "bidirectional"))
      (node (ref "R29") (pin "2") (pinfunction "2_2") (pintype "passive"))
      (node (ref "R30") (pin "1") (pinfunction "1_1") (pintype "passive"))
    )
    (net (code "18") (name "M4_D") (class "Default")
      (node (ref "ARDUINO_DUE1") (pin "25") (pinfunction "25_25") (pintype "bidirectional"))
      (node (ref "Q22") (pin "1") (pinfunction "G_1") (pintype "passive"))
    )
    (net (code "19") (name "M4_I") (class "Default")
      (node (ref "IC1") (pin "11") (pinfunction "X3_11") (pintype "bidirectional"))
      (node (ref "R37") (pin "2") (pinfunction "2_2") (pintype "passive"))
      (node (ref "R38") (pin "1") (pinfunction "1_1") (pintype "passive"))
    )
    (net (code "20") (name "M5_D") (class "Default")
      (node (ref "ARDUINO_DUE1") (pin "26") (pinfunction "26_26") (pintype "bidirectional"))
      (node (ref "Q28") (pin "1") (pinfunction "G_1") (pintype "passive"))
    )
    (net (code "21") (name "M5_I") (class "Default")
      (node (ref "IC1") (pin "1") (pinfunction "Y0_1") (pintype "bidirectional"))
      (node (ref "R45") (pin "2") (pinfunction "2_2") (pintype "passive"))
      (node (ref "R46") (pin "1") (pinfunction "1_1") (pintype "passive"))
    )
    (net (code "22") (name "M6_D") (class "Default")
      (node (ref "ARDUINO_DUE1") (pin "27") (pinfunction "27_27") (pintype "bidirectional"))
      (node (ref "Q34") (pin "1") (pinfunction "G_1") (pintype "passive"))
    )
    (net (code "23") (name "M6_I") (class "Default")
      (node (ref "IC1") (pin "5") (pinfunction "Y1_5") (pintype "bidirectional"))
      (node (ref "R53") (pin "2") (pinfunction "2_2") (pintype "passive"))
      (node (ref "R54") (pin "1") (pinfunction "1_1") (pintype "passive"))
    )
    (net (code "24") (name "M7_D") (class "Default")
      (node (ref "ARDUINO_DUE1") (pin "28") (pinfunction "28_28") (pintype "bidirectional"))
      (node (ref "Q42") (pin "1") (pinfunction "G_1") (pintype "passive"))
    )
    (net (code "25") (name "M7_I") (class "Default")
      (node (ref "IC1") (pin "2") (pinfunction "Y2_2") (pintype "bidirectional"))
      (node (ref "R63") (pin "2") (pinfunction "2_2") (pintype "passive"))
      (node (ref "R64") (pin "1") (pinfunction "1_1") (pintype "passive"))
    )
    (net (code "26") (name "M8_D") (class "Default")
      (node (ref "ARDUINO_DUE1") (pin "29") (pinfunction "29_29") (pintype "bidirectional"))
      (node (ref "Q48") (pin "1") (pinfunction "G_1") (pintype "passive"))
    )
    (net (code "27") (name "M8_I") (class "Default")
      (node (ref "IC1") (pin "4") (pinfunction "Y3_4") (pintype "bidirectional"))
      (node (ref "R71") (pin "2") (pinfunction "2_2") (pintype "passive"))
      (node (ref "R72") (pin "1") (pinfunction "1_1") (pintype "passive"))
    )
    (net (code "28") (name "M9_D") (class "Default")
      (node (ref "ARDUINO_DUE1") (pin "30") (pinfunction "30_30") (pintype "bidirectional"))
      (node (ref "Q3") (pin "1") (pinfunction "G_1") (pintype "passive"))
    )
    (net (code "29") (name "M9_I") (class "Default")
      (node (ref "IC2") (pin "12") (pinfunction "X0_12") (pintype "bidirectional"))
      (node (ref "R13") (pin "2") (pinfunction "2_2") (pintype "passive"))
      (node (ref "R14") (pin "1") (pinfunction "1_1") (pintype "passive"))
    )
    (net (code "30") (name "M10_D") (class "Default")
      (node (ref "ARDUINO_DUE1") (pin "31") (pinfunction "31_31") (pintype "bidirectional"))
      (node (ref "Q9") (pin "1") (pinfunction "G_1") (pintype "passive"))
    )
    (net (code "31") (name "M10_I") (class "Default")
      (node (ref "IC2") (pin "14") (pinfunction "X1_14") (pintype "bidirectional"))
      (node (ref "R21") (pin "2") (pinfunction "2_2") (pintype "passive"))
      (node (ref "R22") (pin "1") (pinfunction "1_1") (pintype "passive"))
    )
    (net (code "32") (name "M11_D") (class "Default")
      (node (ref "ARDUINO_DUE1") (pin "32") (pinfunction "32_32") (pintype "bidirectional"))
      (node (ref "Q17") (pin "1") (pinfunction "G_1") (pintype "passive"))
    )
    (net (code "33") (name "M11_I") (class "Default")
      (node (ref "IC2") (pin "15") (pinfunction "X2_15") (pintype "bidirectional"))
      (node (ref "R31") (pin "2") (pinfunction "2_2") (pintype "passive"))
      (node (ref "R32") (pin "1") (pinfunction "1_1") (pintype "passive"))
    )
    (net (code "34") (name "M12_D") (class "Default")
      (node (ref "ARDUINO_DUE1") (pin "33") (pinfunction "33_33") (pintype "bidirectional"))
      (node (ref "Q23") (pin "1") (pinfunction "G_1") (pintype "passive"))
    )
    (net (code "35") (name "M12_I") (class "Default")
      (node (ref "IC2") (pin "11") (pinfunction "X3_11") (pintype "bidirectional"))
      (node (ref "R39") (pin "2") (pinfunction "2_2") (pintype "passive"))
      (node (ref "R40") (pin "1") (pinfunction "1_1") (pintype "passive"))
    )
    (net (code "36") (name "M13_D") (class "Default")
      (node (ref "ARDUINO_DUE1") (pin "34") (pinfunction "34_34") (pintype "bidirectional"))
      (node (ref "Q29") (pin "1") (pinfunction "G_1") (pintype "passive"))
    )
    (net (code "37") (name "M13_I") (class "Default")
      (node (ref "IC2") (pin "1") (pinfunction "Y0_1") (pintype "bidirectional"))
      (node (ref "R47") (pin "2") (pinfunction "2_2") (pintype "passive"))
      (node (ref "R48") (pin "1") (pinfunction "1_1") (pintype "passive"))
    )
    (net (code "38") (name "M14_D") (class "Default")
      (node (ref "ARDUINO_DUE1") (pin "35") (pinfunction "35_35") (pintype "bidirectional"))
      (node (ref "Q35") (pin "1") (pinfunction "G_1") (pintype "passive"))
    )
    (net (code "39") (name "M14_I") (class "Default")
      (node (ref "IC2") (pin "5") (pinfunction "Y1_5") (pintype "bidirectional"))
      (node (ref "R55") (pin "2") (pinfunction "2_2") (pintype "passive"))
      (node (ref "R56") (pin "1") (pinfunction "1_1") (pintype "passive"))
    )
    (net (code "40") (name "M14_US") (class "Default")
      (node (ref "ARDUINO_DUE1") (pin "50") (pinfunction "50_50") (pintype "bidirectional"))
      (node (ref "Q14") (pin "2") (pinfunction "D_2") (pintype "passive"))
      (node (ref "Q14") (pin "4") (pinfunction "D_4") (pintype "passive"))
      (node (ref "R23") (pin "1") (pinfunction "1_1") (pintype "passive"))
    )
    (net (code "41") (name "M15_D") (class "Default")
      (node (ref "ARDUINO_DUE1") (pin "36") (pinfunction "36_36") (pintype "bidirectional"))
      (node (ref "Q43") (pin "1") (pinfunction "G_1") (pintype "passive"))
    )
    (net (code "42") (name "M15_I") (class "Default")
      (node (ref "IC2") (pin "2") (pinfunction "Y2_2") (pintype "bidirectional"))
      (node (ref "R65") (pin "2") (pinfunction "2_2") (pintype "passive"))
      (node (ref "R66") (pin "1") (pinfunction "1_1") (pintype "passive"))
    )
    (net (code "43") (name "M16_D") (class "Default")
      (node (ref "ARDUINO_DUE1") (pin "37") (pinfunction "37_37") (pintype "bidirectional"))
      (node (ref "Q49") (pin "1") (pinfunction "G_1") (pintype "passive"))
    )
    (net (code "44") (name "M16_I") (class "Default")
      (node (ref "IC2") (pin "4") (pinfunction "Y3_4") (pintype "bidirectional"))
      (node (ref "R73") (pin "2") (pinfunction "2_2") (pintype "passive"))
      (node (ref "R74") (pin "1") (pinfunction "1_1") (pintype "passive"))
    )
    (net (code "45") (name "M58_US") (class "Default")
      (node (ref "ARDUINO_DUE1") (pin "51") (pinfunction "51_51") (pintype "bidirectional"))
      (node (ref "Q40") (pin "2") (pinfunction "D_2") (pintype "passive"))
      (node (ref "Q40") (pin "4") (pinfunction "D_4") (pintype "passive"))
      (node (ref "R57") (pin "1") (pinfunction "1_1") (pintype "passive"))
    )
    (net (code "46") (name "M912_US") (class "Default")
      (node (ref "ARDUINO_DUE1") (pin "52") (pinfunction "52_52") (pintype "bidirectional"))
      (node (ref "Q15") (pin "2") (pinfunction "D_2") (pintype "passive"))
      (node (ref "Q15") (pin "4") (pinfunction "D_4") (pintype "passive"))
      (node (ref "R24") (pin "1") (pinfunction "1_1") (pintype "passive"))
    )
    (net (code "47") (name "M1316_US") (class "Default")
      (node (ref "ARDUINO_DUE1") (pin "53") (pinfunction "53_53") (pintype "bidirectional"))
      (node (ref "Q41") (pin "2") (pinfunction "D_2") (pintype "passive"))
      (node (ref "Q41") (pin "4") (pinfunction "D_4") (pintype "passive"))
      (node (ref "R58") (pin "1") (pinfunction "1_1") (pintype "passive"))
    )
    (net (code "48") (name "MUX1_S1") (class "Default")
      (node (ref "ARDUINO_DUE1") (pin "A0") (pinfunction "AN0_A0") (pintype "bidirectional"))
      (node (ref "IC1") (pin "13") (pinfunction "X_13") (pintype "bidirectional"))
    )
    (net (code "49") (name "MUX1_S2") (class "Default")
      (node (ref "ARDUINO_DUE1") (pin "A1") (pinfunction "AN1_A1") (pintype "bidirectional"))
      (node (ref "IC1") (pin "3") (pinfunction "Y_3") (pintype "bidirectional"))
    )
    (net (code "50") (name "MUX2_S1") (class "Default")
      (node (ref "ARDUINO_DUE1") (pin "A2") (pinfunction "AN2_A2") (pintype "bidirectional"))
      (node (ref "IC2") (pin "13") (pinfunction "X_13") (pintype "bidirectional"))
    )
    (net (code "51") (name "MUX2_S2") (class "Default")
      (node (ref "ARDUINO_DUE1") (pin "A3") (pinfunction "AN3_A3") (pintype "bidirectional"))
      (node (ref "IC2") (pin "3") (pinfunction "Y_3") (pintype "bidirectional"))
    )
    (net (code "52") (name "MUXLV_A") (class "Default")
      (node (ref "ARDUINO_DUE1") (pin "2") (pinfunction "2_2") (pintype "bidirectional"))
      (node (ref "IC1") (pin "10") (pinfunction "A_10") (pintype "input"))
      (node (ref "IC2") (pin "10") (pinfunction "A_10") (pintype "input"))
    )
    (net (code "53") (name "MUXLV_B") (class "Default")
      (node (ref "ARDUINO_DUE1") (pin "3") (pinfunction "3_3") (pintype "bidirectional"))
      (node (ref "IC1") (pin "9") (pinfunction "B_9") (pintype "input"))
      (node (ref "IC2") (pin "9") (pinfunction "B_9") (pintype "input"))
    )
    (net (code "54") (name "MUX_E") (class "Default")
      (node (ref "ARDUINO_DUE1") (pin "4") (pinfunction "4_4") (pintype "bidirectional"))
      (node (ref "IC1") (pin "6") (pinfunction "ENA_6") (pintype "input"))
      (node (ref "IC2") (pin "6") (pinfunction "ENA_6") (pintype "input"))
    )
    (net (code "55") (name "M_RD") (class "Default")
      (node (ref "ARDUINO_DUE1") (pin "5") (pinfunction "5_5") (pintype "bidirectional"))
      (node (ref "Q1") (pin "1") (pinfunction "G_1") (pintype "passive"))
    )
    (net (code "56") (name "Net-(J1D-S)") (class "Default")
      (node (ref "F1") (pin "2") (pinfunction "2_2") (pintype "passive"))
      (node (ref "J1") (pin "4") (pinfunction "S_4") (pintype "passive"))
    )
    (net (code "57") (name "Net-(Q4-D)") (class "Default")
      (node (ref "Q4") (pin "4") (pinfunction "D_4") (pintype "passive"))
      (node (ref "R11") (pin "1") (pinfunction "1_1") (pintype "passive"))
      (node (ref "R9") (pin "2") (pinfunction "2_2") (pintype "passive"))
      (node (ref "X1") (pin "7") (pinfunction "S_7") (pintype "passive"))
    )
    (net (code "58") (name "Net-(Q4-G)") (class "Default")
      (node (ref "Q2") (pin "2") (pinfunction "D_2") (pintype "passive"))
      (node (ref "Q2") (pin "4") (pinfunction "D_4") (pintype "passive"))
      (node (ref "Q4") (pin "1") (pinfunction "G_1") (pintype "passive"))
      (node (ref "R7") (pin "1") (pinfunction "1_1") (pintype "passive"))
    )
    (net (code "59") (name "Net-(Q5-D)") (class "Default")
      (node (ref "Q5") (pin "4") (pinfunction "D_4") (pintype "passive"))
      (node (ref "R10") (pin "2") (pinfunction "2_2") (pintype "passive"))
      (node (ref "R13") (pin "1") (pinfunction "1_1") (pintype "passive"))
      (node (ref "X3") (pin "7") (pinfunction "S_7") (pintype "passive"))
    )
    (net (code "60") (name "Net-(Q5-G)") (class "Default")
      (node (ref "Q3") (pin "2") (pinfunction "D_2") (pintype "passive"))
      (node (ref "Q3") (pin "4") (pinfunction "D_4") (pintype "passive"))
      (node (ref "Q5") (pin "1") (pinfunction "G_1") (pintype "passive"))
      (node (ref "R8") (pin "1") (pinfunction "1_1") (pintype "passive"))
    )
    (net (code "61") (name "Net-(Q6-D-Pad2)") (class "Default")
      (node (ref "Q6") (pin "2") (pinfunction "D_2") (pintype "passive"))
      (node (ref "Q6") (pin "4") (pinfunction "D_4") (pintype "passive"))
      (node (ref "R9") (pin "1") (pinfunction "1_1") (pintype "passive"))
    )
    (net (code "62") (name "Net-(Q7-D-Pad2)") (class "Default")
      (node (ref "Q7") (pin "2") (pinfunction "D_2") (pintype "passive"))
      (node (ref "Q7") (pin "4") (pinfunction "D_4") (pintype "passive"))
      (node (ref "R10") (pin "1") (pinfunction "1_1") (pintype "passive"))
    )
    (net (code "63") (name "Net-(Q10-D)") (class "Default")
      (node (ref "Q10") (pin "4") (pinfunction "D_4") (pintype "passive"))
      (node (ref "R17") (pin "2") (pinfunction "2_2") (pintype "passive"))
      (node (ref "R19") (pin "1") (pinfunction "1_1") (pintype "passive"))
      (node (ref "X1") (pin "6") (pinfunction "S_6") (pintype "passive"))
    )
    (net (code "64") (name "Net-(Q10-G)") (class "Default")
      (node (ref "Q10") (pin "1") (pinfunction "G_1") (pintype "passive"))
      (node (ref "Q8") (pin "2") (pinfunction "D_2") (pintype "passive"))
      (node (ref "Q8") (pin "4") (pinfunction "D_4") (pintype "passive"))
      (node (ref "R15") (pin "1") (pinfunction "1_1") (pintype "passive"))
    )
    (net (code "65") (name "Net-(Q11-D)") (class "Default")
      (node (ref "Q11") (pin "4") (pinfunction "D_4") (pintype "passive"))
      (node (ref "R18") (pin "2") (pinfunction "2_2") (pintype "passive"))
      (node (ref "R21") (pin "1") (pinfunction "1_1") (pintype "passive"))
      (node (ref "X3") (pin "6") (pinfunction "S_6") (pintype "passive"))
    )
    (net (code "66") (name "Net-(Q11-G)") (class "Default")
      (node (ref "Q11") (pin "1") (pinfunction "G_1") (pintype "passive"))
      (node (ref "Q9") (pin "2") (pinfunction "D_2") (pintype "passive"))
      (node (ref "Q9") (pin "4") (pinfunction "D_4") (pintype "passive"))
      (node (ref "R16") (pin "1") (pinfunction "1_1") (pintype "passive"))
    )
    (net (code "67") (name "Net-(Q12-D-Pad2)") (class "Default")
      (node (ref "Q12") (pin "2") (pinfunction "D_2") (pintype "passive"))
      (node (ref "Q12") (pin "4") (pinfunction "D_4") (pintype "passive"))
      (node (ref "R17") (pin "1") (pinfunction "1_1") (pintype "passive"))
    )
    (net (code "68") (name "Net-(Q12-G)") (class "Default")
      (node (ref "Q1") (pin "2") (pinfunction "D_2") (pintype "passive"))
      (node (ref "Q1") (pin "4") (pinfunction "D_4") (pintype "passive"))
      (node (ref "Q12") (pin "1") (pinfunction "G_1") (pintype "passive"))
      (node (ref "Q13") (pin "1") (pinfunction "G_1") (pintype "passive"))
      (node (ref "Q20") (pin "1") (pinfunction "G_1") (pintype "passive"))
      (node (ref "Q21") (pin "1") (pinfunction "G_1") (pintype "passive"))
      (node (ref "Q26") (pin "1") (pinfunction "G_1") (pintype "passive"))
      (node (ref "Q27") (pin "1") (pinfunction "G_1") (pintype "passive"))
      (node (ref "Q32") (pin "1") (pinfunction "G_1") (pintype "passive"))
      (node (ref "Q33") (pin "1") (pinfunction "G_1") (pintype "passive"))
      (node (ref "Q38") (pin "1") (pinfunction "G_1") (pintype "passive"))
      (node (ref "Q39") (pin "1") (pinfunction "G_1") (pintype "passive"))
      (node (ref "Q46") (pin "1") (pinfunction "G_1") (pintype "passive"))
      (node (ref "Q47") (pin "1") (pinfunction "G_1") (pintype "passive"))
      (node (ref "Q52") (pin "1") (pinfunction "G_1") (pintype "passive"))
      (node (ref "Q53") (pin "1") (pinfunction "G_1") (pintype "passive"))
      (node (ref "Q6") (pin "1") (pinfunction "G_1") (pintype "passive"))
      (node (ref "Q7") (pin "1") (pinfunction "G_1") (pintype "passive"))
      (node (ref "R3") (pin "1") (pinfunction "1_1") (pintype "passive"))
      (node (ref "R4") (pin "1") (pinfunction "1_1") (pintype "passive"))
      (node (ref "R5") (pin "1") (pinfunction "1_1") (pintype "passive"))
      (node (ref "R6") (pin "1") (pinfunction "1_1") (pintype "passive"))
    )
    (net (code "69") (name "Net-(Q13-D-Pad2)") (class "Default")
      (node (ref "Q13") (pin "2") (pinfunction "D_2") (pintype "passive"))
      (node (ref "Q13") (pin "4") (pinfunction "D_4") (pintype "passive"))
      (node (ref "R18") (pin "1") (pinfunction "1_1") (pintype "passive"))
    )
    (net (code "70") (name "Net-(Q14-G)") (class "Default")
      (node (ref "Q14") (pin "1") (pinfunction "G_1") (pintype "passive"))
      (node (ref "X1") (pin "3") (pinfunction "S_3") (pintype "passive"))
    )
    (net (code "71") (name "Net-(Q15-G)") (class "Default")
      (node (ref "Q15") (pin "1") (pinfunction "G_1") (pintype "passive"))
      (node (ref "X3") (pin "3") (pinfunction "S_3") (pintype "passive"))
    )
    (net (code "72") (name "Net-(Q18-D)") (class "Default")
      (node (ref "Q18") (pin "4") (pinfunction "D_4") (pintype "passive"))
      (node (ref "R27") (pin "2") (pinfunction "2_2") (pintype "passive"))
      (node (ref "R29") (pin "1") (pinfunction "1_1") (pintype "passive"))
      (node (ref "X1") (pin "5") (pinfunction "S_5") (pintype "passive"))
    )
    (net (code "73") (name "Net-(Q18-G)") (class "Default")
      (node (ref "Q16") (pin "2") (pinfunction "D_2") (pintype "passive"))
      (node (ref "Q16") (pin "4") (pinfunction "D_4") (pintype "passive"))
      (node (ref "Q18") (pin "1") (pinfunction "G_1") (pintype "passive"))
      (node (ref "R25") (pin "1") (pinfunction "1_1") (pintype "passive"))
    )
    (net (code "74") (name "Net-(Q19-D)") (class "Default")
      (node (ref "Q19") (pin "4") (pinfunction "D_4") (pintype "passive"))
      (node (ref "R28") (pin "2") (pinfunction "2_2") (pintype "passive"))
      (node (ref "R31") (pin "1") (pinfunction "1_1") (pintype "passive"))
      (node (ref "X3") (pin "5") (pinfunction "S_5") (pintype "passive"))
    )
    (net (code "75") (name "Net-(Q19-G)") (class "Default")
      (node (ref "Q17") (pin "2") (pinfunction "D_2") (pintype "passive"))
      (node (ref "Q17") (pin "4") (pinfunction "D_4") (pintype "passive"))
      (node (ref "Q19") (pin "1") (pinfunction "G_1") (pintype "passive"))
      (node (ref "R26") (pin "1") (pinfunction "1_1") (pintype "passive"))
    )
    (net (code "76") (name "Net-(Q20-D-Pad2)") (class "Default")
      (node (ref "Q20") (pin "2") (pinfunction "D_2") (pintype "passive"))
      (node (ref "Q20") (pin "4") (pinfunction "D_4") (pintype "passive"))
      (node (ref "R27") (pin "1") (pinfunction "1_1") (pintype "passive"))
    )
    (net (code "77") (name "Net-(Q21-D-Pad2)") (class "Default")
      (node (ref "Q21") (pin "2") (pinfunction "D_2") (pintype "passive"))
      (node (ref "Q21") (pin "4") (pinfunction "D_4") (pintype "passive"))
      (node (ref "R28") (pin "1") (pinfunction "1_1") (pintype "passive"))
    )
    (net (code "78") (name "Net-(Q24-D)") (class "Default")
      (node (ref "Q24") (pin "4") (pinfunction "D_4") (pintype "passive"))
      (node (ref "R35") (pin "2") (pinfunction "2_2") (pintype "passive"))
      (node (ref "R37") (pin "1") (pinfunction "1_1") (pintype "passive"))
      (node (ref "X1") (pin "4") (pinfunction "S_4") (pintype "passive"))
    )
    (net (code "79") (name "Net-(Q24-G)") (class "Default")
      (node (ref "Q22") (pin "2") (pinfunction "D_2") (pintype "passive"))
      (node (ref "Q22") (pin "4") (pinfunction "D_4") (pintype "passive"))
      (node (ref "Q24") (pin "1") (pinfunction "G_1") (pintype "passive"))
      (node (ref "R33") (pin "1") (pinfunction "1_1") (pintype "passive"))
    )
    (net (code "80") (name "Net-(Q25-D)") (class "Default")
      (node (ref "Q25") (pin "4") (pinfunction "D_4") (pintype "passive"))
      (node (ref "R36") (pin "2") (pinfunction "2_2") (pintype "passive"))
      (node (ref "R39") (pin "1") (pinfunction "1_1") (pintype "passive"))
      (node (ref "X3") (pin "4") (pinfunction "S_4") (pintype "passive"))
    )
    (net (code "81") (name "Net-(Q25-G)") (class "Default")
      (node (ref "Q23") (pin "2") (pinfunction "D_2") (pintype "passive"))
      (node (ref "Q23") (pin "4") (pinfunction "D_4") (pintype "passive"))
      (node (ref "Q25") (pin "1") (pinfunction "G_1") (pintype "passive"))
      (node (ref "R34") (pin "1") (pinfunction "1_1") (pintype "passive"))
    )
    (net (code "82") (name "Net-(Q26-D-Pad2)") (class "Default")
      (node (ref "Q26") (pin "2") (pinfunction "D_2") (pintype "passive"))
      (node (ref "Q26") (pin "4") (pinfunction "D_4") (pintype "passive"))
      (node (ref "R35") (pin "1") (pinfunction "1_1") (pintype "passive"))
    )
    (net (code "83") (name "Net-(Q27-D-Pad2)") (class "Default")
      (node (ref "Q27") (pin "2") (pinfunction "D_2") (pintype "passive"))
      (node (ref "Q27") (pin "4") (pinfunction "D_4") (pintype "passive"))
      (node (ref "R36") (pin "1") (pinfunction "1_1") (pintype "passive"))
    )
    (net (code "84") (name "Net-(Q30-D)") (class "Default")
      (node (ref "Q30") (pin "4") (pinfunction "D_4") (pintype "passive"))
      (node (ref "R43") (pin "2") (pinfunction "2_2") (pintype "passive"))
      (node (ref "R45") (pin "1") (pinfunction "1_1") (pintype "passive"))
      (node (ref "X2") (pin "7") (pinfunction "S_7") (pintype "passive"))
    )
    (net (code "85") (name "Net-(Q30-G)") (class "Default")
      (node (ref "Q28") (pin "2") (pinfunction "D_2") (pintype "passive"))
      (node (ref "Q28") (pin "4") (pinfunction "D_4") (pintype "passive"))
      (node (ref "Q30") (pin "1") (pinfunction "G_1") (pintype "passive"))
      (node (ref "R41") (pin "1") (pinfunction "1_1") (pintype "passive"))
    )
    (net (code "86") (name "Net-(Q31-D)") (class "Default")
      (node (ref "Q31") (pin "4") (pinfunction "D_4") (pintype "passive"))
      (node (ref "R44") (pin "2") (pinfunction "2_2") (pintype "passive"))
      (node (ref "R47") (pin "1") (pinfunction "1_1") (pintype "passive"))
      (node (ref "X4") (pin "7") (pinfunction "S_7") (pintype "passive"))
    )
    (net (code "87") (name "Net-(Q31-G)") (class "Default")
      (node (ref "Q29") (pin "2") (pinfunction "D_2") (pintype "passive"))
      (node (ref "Q29") (pin "4") (pinfunction "D_4") (pintype "passive"))
      (node (ref "Q31") (pin "1") (pinfunction "G_1") (pintype "passive"))
      (node (ref "R42") (pin "1") (pinfunction "1_1") (pintype "passive"))
    )
    (net (code "88") (name "Net-(Q32-D-Pad2)") (class "Default")
      (node (ref "Q32") (pin "2") (pinfunction "D_2") (pintype "passive"))
      (node (ref "Q32") (pin "4") (pinfunction "D_4") (pintype "passive"))
      (node (ref "R43") (pin "1") (pinfunction "1_1") (pintype "passive"))
    )
    (net (code "89") (name "Net-(Q33-D-Pad2)") (class "Default")
      (node (ref "Q33") (pin "2") (pinfunction "D_2") (pintype "passive"))
      (node (ref "Q33") (pin "4") (pinfunction "D_4") (pintype "passive"))
      (node (ref "R44") (pin "1") (pinfunction "1_1") (pintype "passive"))
    )
    (net (code "90") (name "Net-(Q36-D)") (class "Default")
      (node (ref "Q36") (pin "4") (pinfunction "D_4") (pintype "passive"))
      (node (ref "R51") (pin "2") (pinfunction "2_2") (pintype "passive"))
      (node (ref "R53") (pin "1") (pinfunction "1_1") (pintype "passive"))
      (node (ref "X2") (pin "6") (pinfunction "S_6") (pintype "passive"))
    )
    (net (code "91") (name "Net-(Q36-G)") (class "Default")
      (node (ref "Q34") (pin "2") (pinfunction "D_2") (pintype "passive"))
      (node (ref "Q34") (pin "4") (pinfunction "D_4") (pintype "passive"))
      (node (ref "Q36") (pin "1") (pinfunction "G_1") (pintype "passive"))
      (node (ref "R49") (pin "1") (pinfunction "1_1") (pintype "passive"))
    )
    (net (code "92") (name "Net-(Q37-D)") (class "Default")
      (node (ref "Q37") (pin "4") (pinfunction "D_4") (pintype "passive"))
      (node (ref "R52") (pin "2") (pinfunction "2_2") (pintype "passive"))
      (node (ref "R55") (pin "1") (pinfunction "1_1") (pintype "passive"))
      (node (ref "X4") (pin "6") (pinfunction "S_6") (pintype "passive"))
    )
    (net (code "93") (name "Net-(Q37-G)") (class "Default")
      (node (ref "Q35") (pin "2") (pinfunction "D_2") (pintype "passive"))
      (node (ref "Q35") (pin "4") (pinfunction "D_4") (pintype "passive"))
      (node (ref "Q37") (pin "1") (pinfunction "G_1") (pintype "passive"))
      (node (ref "R50") (pin "1") (pinfunction "1_1") (pintype "passive"))
    )
    (net (code "94") (name "Net-(Q38-D-Pad2)") (class "Default")
      (node (ref "Q38") (pin "2") (pinfunction "D_2") (pintype "passive"))
      (node (ref "Q38") (pin "4") (pinfunction "D_4") (pintype "passive"))
      (node (ref "R51") (pin "1") (pinfunction "1_1") (pintype "passive"))
    )
    (net (code "95") (name "Net-(Q39-D-Pad2)") (class "Default")
      (node (ref "Q39") (pin "2") (pinfunction "D_2") (pintype "passive"))
      (node (ref "Q39") (pin "4") (pinfunction "D_4") (pintype "passive"))
      (node (ref "R52") (pin "1") (pinfunction "1_1") (pintype "passive"))
    )
    (net (code "96") (name "Net-(Q40-G)") (class "Default")
      (node (ref "Q40") (pin "1") (pinfunction "G_1") (pintype "passive"))
      (node (ref "X2") (pin "3") (pinfunction "S_3") (pintype "passive"))
    )
    (net (code "97") (name "Net-(Q41-G)") (class "Default")
      (node (ref "Q41") (pin "1") (pinfunction "G_1") (pintype "passive"))
      (node (ref "X4") (pin "3") (pinfunction "S_3") (pintype "passive"))
    )
    (net (code "98") (name "Net-(Q44-D)") (class "Default")
      (node (ref "Q44") (pin "4") (pinfunction "D_4") (pintype "passive"))
      (node (ref "R61") (pin "2") (pinfunction "2_2") (pintype "passive"))
      (node (ref "R63") (pin "1") (pinfunction "1_1") (pintype "passive"))
      (node (ref "X2") (pin "5") (pinfunction "S_5") (pintype "passive"))
    )
    (net (code "99") (name "Net-(Q44-G)") (class "Default")
      (node (ref "Q42") (pin "2") (pinfunction "D_2") (pintype "passive"))
      (node (ref "Q42") (pin "4") (pinfunction "D_4") (pintype "passive"))
      (node (ref "Q44") (pin "1") (pinfunction "G_1") (pintype "passive"))
      (node (ref "R59") (pin "1") (pinfunction "1_1") (pintype "passive"))
    )
    (net (code "100") (name "Net-(Q45-D)") (class "Default")
      (node (ref "Q45") (pin "4") (pinfunction "D_4") (pintype "passive"))
      (node (ref "R62") (pin "2") (pinfunction "2_2") (pintype "passive"))
      (node (ref "R65") (pin "1") (pinfunction "1_1") (pintype "passive"))
      (node (ref "X4") (pin "5") (pinfunction "S_5") (pintype "passive"))
    )
    (net (code "101") (name "Net-(Q45-G)") (class "Default")
      (node (ref "Q43") (pin "2") (pinfunction "D_2") (pintype "passive"))
      (node (ref "Q43") (pin "4") (pinfunction "D_4") (pintype "passive"))
      (node (ref "Q45") (pin "1") (pinfunction "G_1") (pintype "passive"))
      (node (ref "R60") (pin "1") (pinfunction "1_1") (pintype "passive"))
    )
    (net (code "102") (name "Net-(Q46-D-Pad2)") (class "Default")
      (node (ref "Q46") (pin "2") (pinfunction "D_2") (pintype "passive"))
      (node (ref "Q46") (pin "4") (pinfunction "D_4") (pintype "passive"))
      (node (ref "R61") (pin "1") (pinfunction "1_1") (pintype "passive"))
    )
    (net (code "103") (name "Net-(Q47-D-Pad2)") (class "Default")
      (node (ref "Q47") (pin "2") (pinfunction "D_2") (pintype "passive"))
      (node (ref "Q47") (pin "4") (pinfunction "D_4") (pintype "passive"))
      (node (ref "R62") (pin "1") (pinfunction "1_1") (pintype "passive"))
    )
    (net (code "104") (name "Net-(Q50-D)") (class "Default")
      (node (ref "Q50") (pin "4") (pinfunction "D_4") (pintype "passive"))
      (node (ref "R69") (pin "2") (pinfunction "2_2") (pintype "passive"))
      (node (ref "R71") (pin "1") (pinfunction "1_1") (pintype "passive"))
      (node (ref "X2") (pin "4") (pinfunction "S_4") (pintype "passive"))
    )
    (net (code "105") (name "Net-(Q50-G)") (class "Default")
      (node (ref "Q48") (pin "2") (pinfunction "D_2") (pintype "passive"))
      (node (ref "Q48") (pin "4") (pinfunction "D_4") (pintype "passive"))
      (node (ref "Q50") (pin "1") (pinfunction "G_1") (pintype "passive"))
      (node (ref "R67") (pin "1") (pinfunction "1_1") (pintype "passive"))
    )
    (net (code "106") (name "Net-(Q51-D)") (class "Default")
      (node (ref "Q51") (pin "4") (pinfunction "D_4") (pintype "passive"))
      (node (ref "R70") (pin "2") (pinfunction "2_2") (pintype "passive"))
      (node (ref "R73") (pin "1") (pinfunction "1_1") (pintype "passive"))
      (node (ref "X4") (pin "4") (pinfunction "S_4") (pintype "passive"))
    )
    (net (code "107") (name "Net-(Q51-G)") (class "Default")
      (node (ref "Q49") (pin "2") (pinfunction "D_2") (pintype "passive"))
      (node (ref "Q49") (pin "4") (pinfunction "D_4") (pintype "passive"))
      (node (ref "Q51") (pin "1") (pinfunction "G_1") (pintype "passive"))
      (node (ref "R68") (pin "1") (pinfunction "1_1") (pintype "passive"))
    )
    (net (code "108") (name "Net-(Q52-D-Pad2)") (class "Default")
      (node (ref "Q52") (pin "2") (pinfunction "D_2") (pintype "passive"))
      (node (ref "Q52") (pin "4") (pinfunction "D_4") (pintype "passive"))
      (node (ref "R69") (pin "1") (pinfunction "1_1") (pintype "passive"))
    )
    (net (code "109") (name "Net-(Q53-D-Pad2)") (class "Default")
      (node (ref "Q53") (pin "2") (pinfunction "D_2") (pintype "passive"))
      (node (ref "Q53") (pin "4") (pinfunction "D_4") (pintype "passive"))
      (node (ref "R70") (pin "1") (pinfunction "1_1") (pintype "passive"))
    )
    (net (code "110") (name "PSU_U") (class "Default")
      (node (ref "ARDUINO_DUE1") (pin "A5") (pinfunction "AN5_A5") (pintype "bidirectional"))
      (node (ref "R1") (pin "1") (pinfunction "1_1") (pintype "passive"))
      (node (ref "R2") (pin "2") (pinfunction "2_2") (pintype "passive"))
    )
    (net (code "111") (name "SPI_5V") (class "Default")
      (node (ref "ARDUINO_DUE1") (pin "5V_2") (pinfunction "5V_SPI_5V_2") (pintype "bidirectional"))
      (node (ref "JP1") (pin "2") (pinfunction "2_2") (pintype "passive"))
    )
    (net (code "112") (name "S_CLK") (class "Default")
      (node (ref "ARDUINO_DUE1") (pin "SPCK") (pinfunction "SPCK_SPCK") (pintype "bidirectional"))
      (node (ref "JP1") (pin "4") (pinfunction "4_4") (pintype "passive"))
    )
    (net (code "113") (name "S_CS") (class "Default")
      (node (ref "ARDUINO_DUE1") (pin "10") (pinfunction "10_10") (pintype "bidirectional"))
      (node (ref "JP1") (pin "7") (pinfunction "7_7") (pintype "passive"))
    )
    (net (code "114") (name "S_D{slash}C") (class "Default")
      (node (ref "ARDUINO_DUE1") (pin "9") (pinfunction "9_9") (pintype "bidirectional"))
      (node (ref "JP1") (pin "8") (pinfunction "8_8") (pintype "passive"))
    )
    (net (code "115") (name "S_MISO") (class "Default")
      (node (ref "ARDUINO_DUE1") (pin "MISO") (pinfunction "MISO_MISO") (pintype "bidirectional"))
      (node (ref "JP1") (pin "5") (pinfunction "5_5") (pintype "passive"))
    )
    (net (code "116") (name "S_MOSI") (class "Default")
      (node (ref "ARDUINO_DUE1") (pin "MOSI") (pinfunction "MOSI_MOSI") (pintype "bidirectional"))
      (node (ref "JP1") (pin "6") (pinfunction "6_6") (pintype "passive"))
    )
    (net (code "117") (name "S_RST") (class "Default")
      (node (ref "ARDUINO_DUE1") (pin "MASTER_RESET_SPI") (pinfunction "MASTER_R_SPI_MASTER_RESET_SPI") (pintype "bidirectional"))
      (node (ref "JP1") (pin "9") (pinfunction "9_9") (pintype "passive"))
    )
    (net (code "118") (name "S_X+") (class "Default")
      (node (ref "ARDUINO_DUE1") (pin "A10") (pinfunction "AN10_A10") (pintype "bidirectional"))
      (node (ref "JP1") (pin "12") (pinfunction "12_12") (pintype "passive"))
    )
    (net (code "119") (name "S_X-") (class "Default")
      (node (ref "ARDUINO_DUE1") (pin "A11") (pinfunction "AN11_A11") (pintype "bidirectional"))
      (node (ref "JP1") (pin "14") (pinfunction "14_14") (pintype "passive"))
    )
    (net (code "120") (name "S_Y+") (class "Default")
      (node (ref "ARDUINO_DUE1") (pin "A8") (pinfunction "AN8_A8") (pintype "bidirectional"))
      (node (ref "JP1") (pin "11") (pinfunction "11_11") (pintype "passive"))
    )
    (net (code "121") (name "S_Y-") (class "Default")
      (node (ref "ARDUINO_DUE1") (pin "A9") (pinfunction "AN9_A9") (pintype "bidirectional"))
      (node (ref "JP1") (pin "13") (pinfunction "13_13") (pintype "passive"))
    )
    (net (code "122") (name "unconnected-(ARDUINO_DUE1-5V-Pad5V0)") (class "Default")
      (node (ref "ARDUINO_DUE1") (pin "5V0") (pinfunction "5V_5V0") (pintype "bidirectional"))
    )
    (net (code "123") (name "unconnected-(ARDUINO_DUE1-5V-Pad5V0_1)") (class "Default")
      (node (ref "ARDUINO_DUE1") (pin "5V0_1") (pinfunction "5V_5V0_1") (pintype "bidirectional"))
    )
    (net (code "124") (name "unconnected-(ARDUINO_DUE1-5V-Pad5V0_2)") (class "Default")
      (node (ref "ARDUINO_DUE1") (pin "5V0_2") (pinfunction "5V_5V0_2") (pintype "bidirectional"))
    )
    (net (code "125") (name "unconnected-(ARDUINO_DUE1-AN4-PadA4)") (class "Default")
      (node (ref "ARDUINO_DUE1") (pin "A4") (pinfunction "AN4_A4") (pintype "bidirectional"))
    )
    (net (code "126") (name "unconnected-(ARDUINO_DUE1-AN6-PadA6)") (class "Default")
      (node (ref "ARDUINO_DUE1") (pin "A6") (pinfunction "AN6_A6") (pintype "bidirectional"))
    )
    (net (code "127") (name "unconnected-(ARDUINO_DUE1-AN7-PadA7)") (class "Default")
      (node (ref "ARDUINO_DUE1") (pin "A7") (pinfunction "AN7_A7") (pintype "bidirectional"))
    )
    (net (code "128") (name "unconnected-(ARDUINO_DUE1-GND-PadGND_7)") (class "Default")
      (node (ref "ARDUINO_DUE1") (pin "GND_7") (pinfunction "GND_GND_7") (pintype "bidirectional"))
    )
    (net (code "129") (name "unconnected-(ARDUINO_DUE1-GND-PadGND_8)") (class "Default")
      (node (ref "ARDUINO_DUE1") (pin "GND_8") (pinfunction "GND_GND_8") (pintype "bidirectional"))
    )
    (net (code "130") (name "unconnected-(ARDUINO_DUE1-GND-PadGND_9)") (class "Default")
      (node (ref "ARDUINO_DUE1") (pin "GND_9") (pinfunction "GND_GND_9") (pintype "bidirectional"))
    )
    (net (code "131") (name "unconnected-(ARDUINO_DUE1-GND-PadGND_10)") (class "Default")
      (node (ref "ARDUINO_DUE1") (pin "GND_10") (pinfunction "GND_GND_10") (pintype "bidirectional"))
    )
    (net (code "132") (name "unconnected-(ARDUINO_DUE1-MASTER_R_JTAG-PadMASTER_RESET_JTAG)") (class "Default")
      (node (ref "ARDUINO_DUE1") (pin "MASTER_RESET_JTAG") (pinfunction "MASTER_R_JTAG_MASTER_RESET_JTAG") (pintype "bidirectional"))
    )
    (net (code "133") (name "unconnected-(ARDUINO_DUE1-NC-PadNC_2)") (class "Default")
      (node (ref "ARDUINO_DUE1") (pin "NC_2") (pinfunction "NC_NC_2") (pintype "no_connect"))
    )
    (net (code "134") (name "unconnected-(ARDUINO_DUE1-NC-PadNC_5)") (class "Default")
      (node (ref "ARDUINO_DUE1") (pin "NC_5") (pinfunction "NC_NC_5") (pintype "bidirectional"))
    )
    (net (code "135") (name "unconnected-(ARDUINO_DUE1-Pad3V3_JTAG)") (class "Default")
      (node (ref "ARDUINO_DUE1") (pin "3V3_JTAG") (pinfunction "3V3_JTAG_3V3_JTAG") (pintype "bidirectional"))
    )
    (net (code "136") (name "unconnected-(ARDUINO_DUE1-Pad6)") (class "Default")
      (node (ref "ARDUINO_DUE1") (pin "6") (pinfunction "6_6") (pintype "bidirectional"))
    )
    (net (code "137") (name "unconnected-(ARDUINO_DUE1-Pad7)") (class "Default")
      (node (ref "ARDUINO_DUE1") (pin "7") (pinfunction "7_7") (pintype "bidirectional"))
    )
    (net (code "138") (name "unconnected-(ARDUINO_DUE1-Pad13)") (class "Default")
      (node (ref "ARDUINO_DUE1") (pin "13") (pinfunction "13_13") (pintype "bidirectional"))
    )
    (net (code "139") (name "unconnected-(ARDUINO_DUE1-Pad38)") (class "Default")
      (node (ref "ARDUINO_DUE1") (pin "38") (pinfunction "38_38") (pintype "bidirectional"))
    )
    (net (code "140") (name "unconnected-(ARDUINO_DUE1-Pad39)") (class "Default")
      (node (ref "ARDUINO_DUE1") (pin "39") (pinfunction "39_39") (pintype "bidirectional"))
    )
    (net (code "141") (name "unconnected-(ARDUINO_DUE1-Pad40)") (class "Default")
      (node (ref "ARDUINO_DUE1") (pin "40") (pinfunction "40_40") (pintype "bidirectional"))
    )
    (net (code "142") (name "unconnected-(ARDUINO_DUE1-Pad41)") (class "Default")
      (node (ref "ARDUINO_DUE1") (pin "41") (pinfunction "41_41") (pintype "bidirectional"))
    )
    (net (code "143") (name "unconnected-(ARDUINO_DUE1-Pad42)") (class "Default")
      (node (ref "ARDUINO_DUE1") (pin "42") (pinfunction "42_42") (pintype "bidirectional"))
    )
    (net (code "144") (name "unconnected-(ARDUINO_DUE1-Pad43)") (class "Default")
      (node (ref "ARDUINO_DUE1") (pin "43") (pinfunction "43_43") (pintype "bidirectional"))
    )
    (net (code "145") (name "unconnected-(ARDUINO_DUE1-Pad44)") (class "Default")
      (node (ref "ARDUINO_DUE1") (pin "44") (pinfunction "44_44") (pintype "bidirectional"))
    )
    (net (code "146") (name "unconnected-(ARDUINO_DUE1-Pad45)") (class "Default")
      (node (ref "ARDUINO_DUE1") (pin "45") (pinfunction "45_45") (pintype "bidirectional"))
    )
    (net (code "147") (name "unconnected-(ARDUINO_DUE1-Pad46)") (class "Default")
      (node (ref "ARDUINO_DUE1") (pin "46") (pinfunction "46_46") (pintype "bidirectional"))
    )
    (net (code "148") (name "unconnected-(ARDUINO_DUE1-Pad47)") (class "Default")
      (node (ref "ARDUINO_DUE1") (pin "47") (pinfunction "47_47") (pintype "bidirectional"))
    )
    (net (code "149") (name "unconnected-(ARDUINO_DUE1-Pad48)") (class "Default")
      (node (ref "ARDUINO_DUE1") (pin "48") (pinfunction "48_48") (pintype "bidirectional"))
    )
    (net (code "150") (name "unconnected-(ARDUINO_DUE1-Pad49)") (class "Default")
      (node (ref "ARDUINO_DUE1") (pin "49") (pinfunction "49_49") (pintype "bidirectional"))
    )
    (net (code "151") (name "unconnected-(ARDUINO_DUE1-PadAREF)") (class "Default")
      (node (ref "ARDUINO_DUE1") (pin "AREF") (pinfunction "AREF_AREF") (pintype "bidirectional"))
    )
    (net (code "152") (name "unconnected-(ARDUINO_DUE1-PadCANRX)") (class "Default")
      (node (ref "ARDUINO_DUE1") (pin "CANRX") (pinfunction "CANRX_CANRX") (pintype "bidirectional"))
    )
    (net (code "153") (name "unconnected-(ARDUINO_DUE1-PadCANTX)") (class "Default")
      (node (ref "ARDUINO_DUE1") (pin "CANTX") (pinfunction "CANTX_CANTX") (pintype "bidirectional"))
    )
    (net (code "154") (name "unconnected-(ARDUINO_DUE1-PadDAC0)") (class "Default")
      (node (ref "ARDUINO_DUE1") (pin "DAC0") (pinfunction "DAC0_DAC0") (pintype "bidirectional"))
    )
    (net (code "155") (name "unconnected-(ARDUINO_DUE1-PadDAC1)") (class "Default")
      (node (ref "ARDUINO_DUE1") (pin "DAC1") (pinfunction "DAC1_DAC1") (pintype "bidirectional"))
    )
    (net (code "156") (name "unconnected-(ARDUINO_DUE1-PadIOREF)") (class "Default")
      (node (ref "ARDUINO_DUE1") (pin "IOREF") (pinfunction "IOREF_IOREF") (pintype "bidirectional"))
    )
    (net (code "157") (name "unconnected-(ARDUINO_DUE1-PadJTAG_RESET)") (class "Default")
      (node (ref "ARDUINO_DUE1") (pin "JTAG_RESET") (pinfunction "JTAG_RESET_JTAG_RESET") (pintype "bidirectional"))
    )
    (net (code "158") (name "unconnected-(ARDUINO_DUE1-PadJTAG_TCK)") (class "Default")
      (node (ref "ARDUINO_DUE1") (pin "JTAG_TCK") (pinfunction "JTAG_TCK_JTAG_TCK") (pintype "bidirectional"))
    )
    (net (code "159") (name "unconnected-(ARDUINO_DUE1-PadJTAG_TCK_2)") (class "Default")
      (node (ref "ARDUINO_DUE1") (pin "JTAG_TCK_2") (pinfunction "JTAG_TCK_2_JTAG_TCK_2") (pintype "bidirectional"))
    )
    (net (code "160") (name "unconnected-(ARDUINO_DUE1-PadJTAG_TDI)") (class "Default")
      (node (ref "ARDUINO_DUE1") (pin "JTAG_TDI") (pinfunction "JTAG_TDI_JTAG_TDI") (pintype "bidirectional"))
    )
    (net (code "161") (name "unconnected-(ARDUINO_DUE1-PadJTAG_TDO)") (class "Default")
      (node (ref "ARDUINO_DUE1") (pin "JTAG_TDO") (pinfunction "JTAG_TDO_JTAG_TDO") (pintype "bidirectional"))
    )
    (net (code "162") (name "unconnected-(ARDUINO_DUE1-PadJTAG_TMS)") (class "Default")
      (node (ref "ARDUINO_DUE1") (pin "JTAG_TMS") (pinfunction "JTAG_TMS_JTAG_TMS") (pintype "bidirectional"))
    )
    (net (code "163") (name "unconnected-(ARDUINO_DUE1-PadJTAG_TMS_2)") (class "Default")
      (node (ref "ARDUINO_DUE1") (pin "JTAG_TMS_2") (pinfunction "JTAG_TMS_2_JTAG_TMS_2") (pintype "bidirectional"))
    )
    (net (code "164") (name "unconnected-(ARDUINO_DUE1-PadRESET)") (class "Default")
      (node (ref "ARDUINO_DUE1") (pin "RESET") (pinfunction "RESET_RESET") (pintype "bidirectional"))
    )
    (net (code "165") (name "unconnected-(ARDUINO_DUE1-PadRESET2)") (class "Default")
      (node (ref "ARDUINO_DUE1") (pin "RESET2") (pinfunction "RESET2_RESET2") (pintype "bidirectional"))
    )
    (net (code "166") (name "unconnected-(ARDUINO_DUE1-PadSCL1)") (class "Default")
      (node (ref "ARDUINO_DUE1") (pin "SCL1") (pinfunction "SCL1_SCL1") (pintype "bidirectional"))
    )
    (net (code "167") (name "unconnected-(ARDUINO_DUE1-PadSDA1)") (class "Default")
      (node (ref "ARDUINO_DUE1") (pin "SDA1") (pinfunction "SDA1_SDA1") (pintype "bidirectional"))
    )
    (net (code "168") (name "unconnected-(ARDUINO_DUE1-RX0<0-Pad0)") (class "Default")
      (node (ref "ARDUINO_DUE1") (pin "0") (pinfunction "RX0<0_0") (pintype "bidirectional"))
    )
    (net (code "169") (name "unconnected-(ARDUINO_DUE1-RX1_19-Pad19)") (class "Default")
      (node (ref "ARDUINO_DUE1") (pin "19") (pinfunction "RX1_19_19") (pintype "bidirectional"))
    )
    (net (code "170") (name "unconnected-(ARDUINO_DUE1-RX2_17-Pad17)") (class "Default")
      (node (ref "ARDUINO_DUE1") (pin "17") (pinfunction "RX2_17_17") (pintype "bidirectional"))
    )
    (net (code "171") (name "unconnected-(ARDUINO_DUE1-RX3_15-Pad15)") (class "Default")
      (node (ref "ARDUINO_DUE1") (pin "15") (pinfunction "RX3_15_15") (pintype "bidirectional"))
    )
    (net (code "172") (name "unconnected-(ARDUINO_DUE1-SCL_21-Pad21)") (class "Default")
      (node (ref "ARDUINO_DUE1") (pin "21") (pinfunction "SCL_21_21") (pintype "bidirectional"))
    )
    (net (code "173") (name "unconnected-(ARDUINO_DUE1-SDA_20-Pad20)") (class "Default")
      (node (ref "ARDUINO_DUE1") (pin "20") (pinfunction "SDA_20_20") (pintype "bidirectional"))
    )
    (net (code "174") (name "unconnected-(ARDUINO_DUE1-TX0>1-Pad1)") (class "Default")
      (node (ref "ARDUINO_DUE1") (pin "1") (pinfunction "TX0>1_1") (pintype "bidirectional"))
    )
    (net (code "175") (name "unconnected-(ARDUINO_DUE1-TX1_18-Pad18)") (class "Default")
      (node (ref "ARDUINO_DUE1") (pin "18") (pinfunction "TX1_18_18") (pintype "bidirectional"))
    )
    (net (code "176") (name "unconnected-(ARDUINO_DUE1-TX2_16-Pad16)") (class "Default")
      (node (ref "ARDUINO_DUE1") (pin "16") (pinfunction "TX2_16_16") (pintype "bidirectional"))
    )
    (net (code "177") (name "unconnected-(ARDUINO_DUE1-TX3_14-Pad14)") (class "Default")
      (node (ref "ARDUINO_DUE1") (pin "14") (pinfunction "TX3_14_14") (pintype "bidirectional"))
    )
    (net (code "178") (name "unconnected-(J1A-S-Pad1)") (class "Default")
      (node (ref "J1") (pin "1") (pinfunction "S_1") (pintype "passive"))
    )
    (net (code "179") (name "unconnected-(J1B-S-Pad2)") (class "Default")
      (node (ref "J1") (pin "2") (pinfunction "S_2") (pintype "passive"))
    )
    (net (code "180") (name "unconnected-(JP1-Pad3)") (class "Default")
      (node (ref "JP1") (pin "3") (pinfunction "3_3") (pintype "passive"))
    )
    (net (code "181") (name "unconnected-(JP1-Pad10)") (class "Default")
      (node (ref "JP1") (pin "10") (pinfunction "10_10") (pintype "passive"))
    )
    (net (code "182") (name "unconnected-(JP1-Pad15)") (class "Default")
      (node (ref "JP1") (pin "15") (pinfunction "15_15") (pintype "passive"))
    )
    (net (code "183") (name "unconnected-(JP1-Pad16)") (class "Default")
      (node (ref "JP1") (pin "16") (pinfunction "16_16") (pintype "passive"))
    )
    (net (code "184") (name "unconnected-(JP1-Pad17)") (class "Default")
      (node (ref "JP1") (pin "17") (pinfunction "17_17") (pintype "passive"))
    )
    (net (code "185") (name "unconnected-(JP1-Pad18)") (class "Default")
      (node (ref "JP1") (pin "18") (pinfunction "18_18") (pintype "passive"))
    )
    (net (code "186") (name "unconnected-(JP1-Pad19)") (class "Default")
      (node (ref "JP1") (pin "19") (pinfunction "19_19") (pintype "passive"))
    )
    (net (code "187") (name "unconnected-(JP1-Pad20)") (class "Default")
      (node (ref "JP1") (pin "20") (pinfunction "20_20") (pintype "passive"))
    )
    (net (code "188") (name "unconnected-(X1A-S-Pad1)") (class "Default")
      (node (ref "X1") (pin "1") (pinfunction "S_1") (pintype "passive"))
    )
    (net (code "189") (name "unconnected-(X1B-S-Pad2)") (class "Default")
      (node (ref "X1") (pin "2") (pinfunction "S_2") (pintype "passive"))
    )
    (net (code "190") (name "unconnected-(X2A-S-Pad1)") (class "Default")
      (node (ref "X2") (pin "1") (pinfunction "S_1") (pintype "passive"))
    )
    (net (code "191") (name "unconnected-(X2B-S-Pad2)") (class "Default")
      (node (ref "X2") (pin "2") (pinfunction "S_2") (pintype "passive"))
    )
    (net (code "192") (name "unconnected-(X3A-S-Pad1)") (class "Default")
      (node (ref "X3") (pin "1") (pinfunction "S_1") (pintype "passive"))
    )
    (net (code "193") (name "unconnected-(X3B-S-Pad2)") (class "Default")
      (node (ref "X3") (pin "2") (pinfunction "S_2") (pintype "passive"))
    )
    (net (code "194") (name "unconnected-(X4A-S-Pad1)") (class "Default")
      (node (ref "X4") (pin "1") (pinfunction "S_1") (pintype "passive"))
    )
    (net (code "195") (name "unconnected-(X4B-S-Pad2)") (class "Default")
      (node (ref "X4") (pin "2") (pinfunction "S_2") (pintype "passive"))
    )
  )
)
